# dash-hat.net
KiCad netlist of a schematic drawn in EAGLE
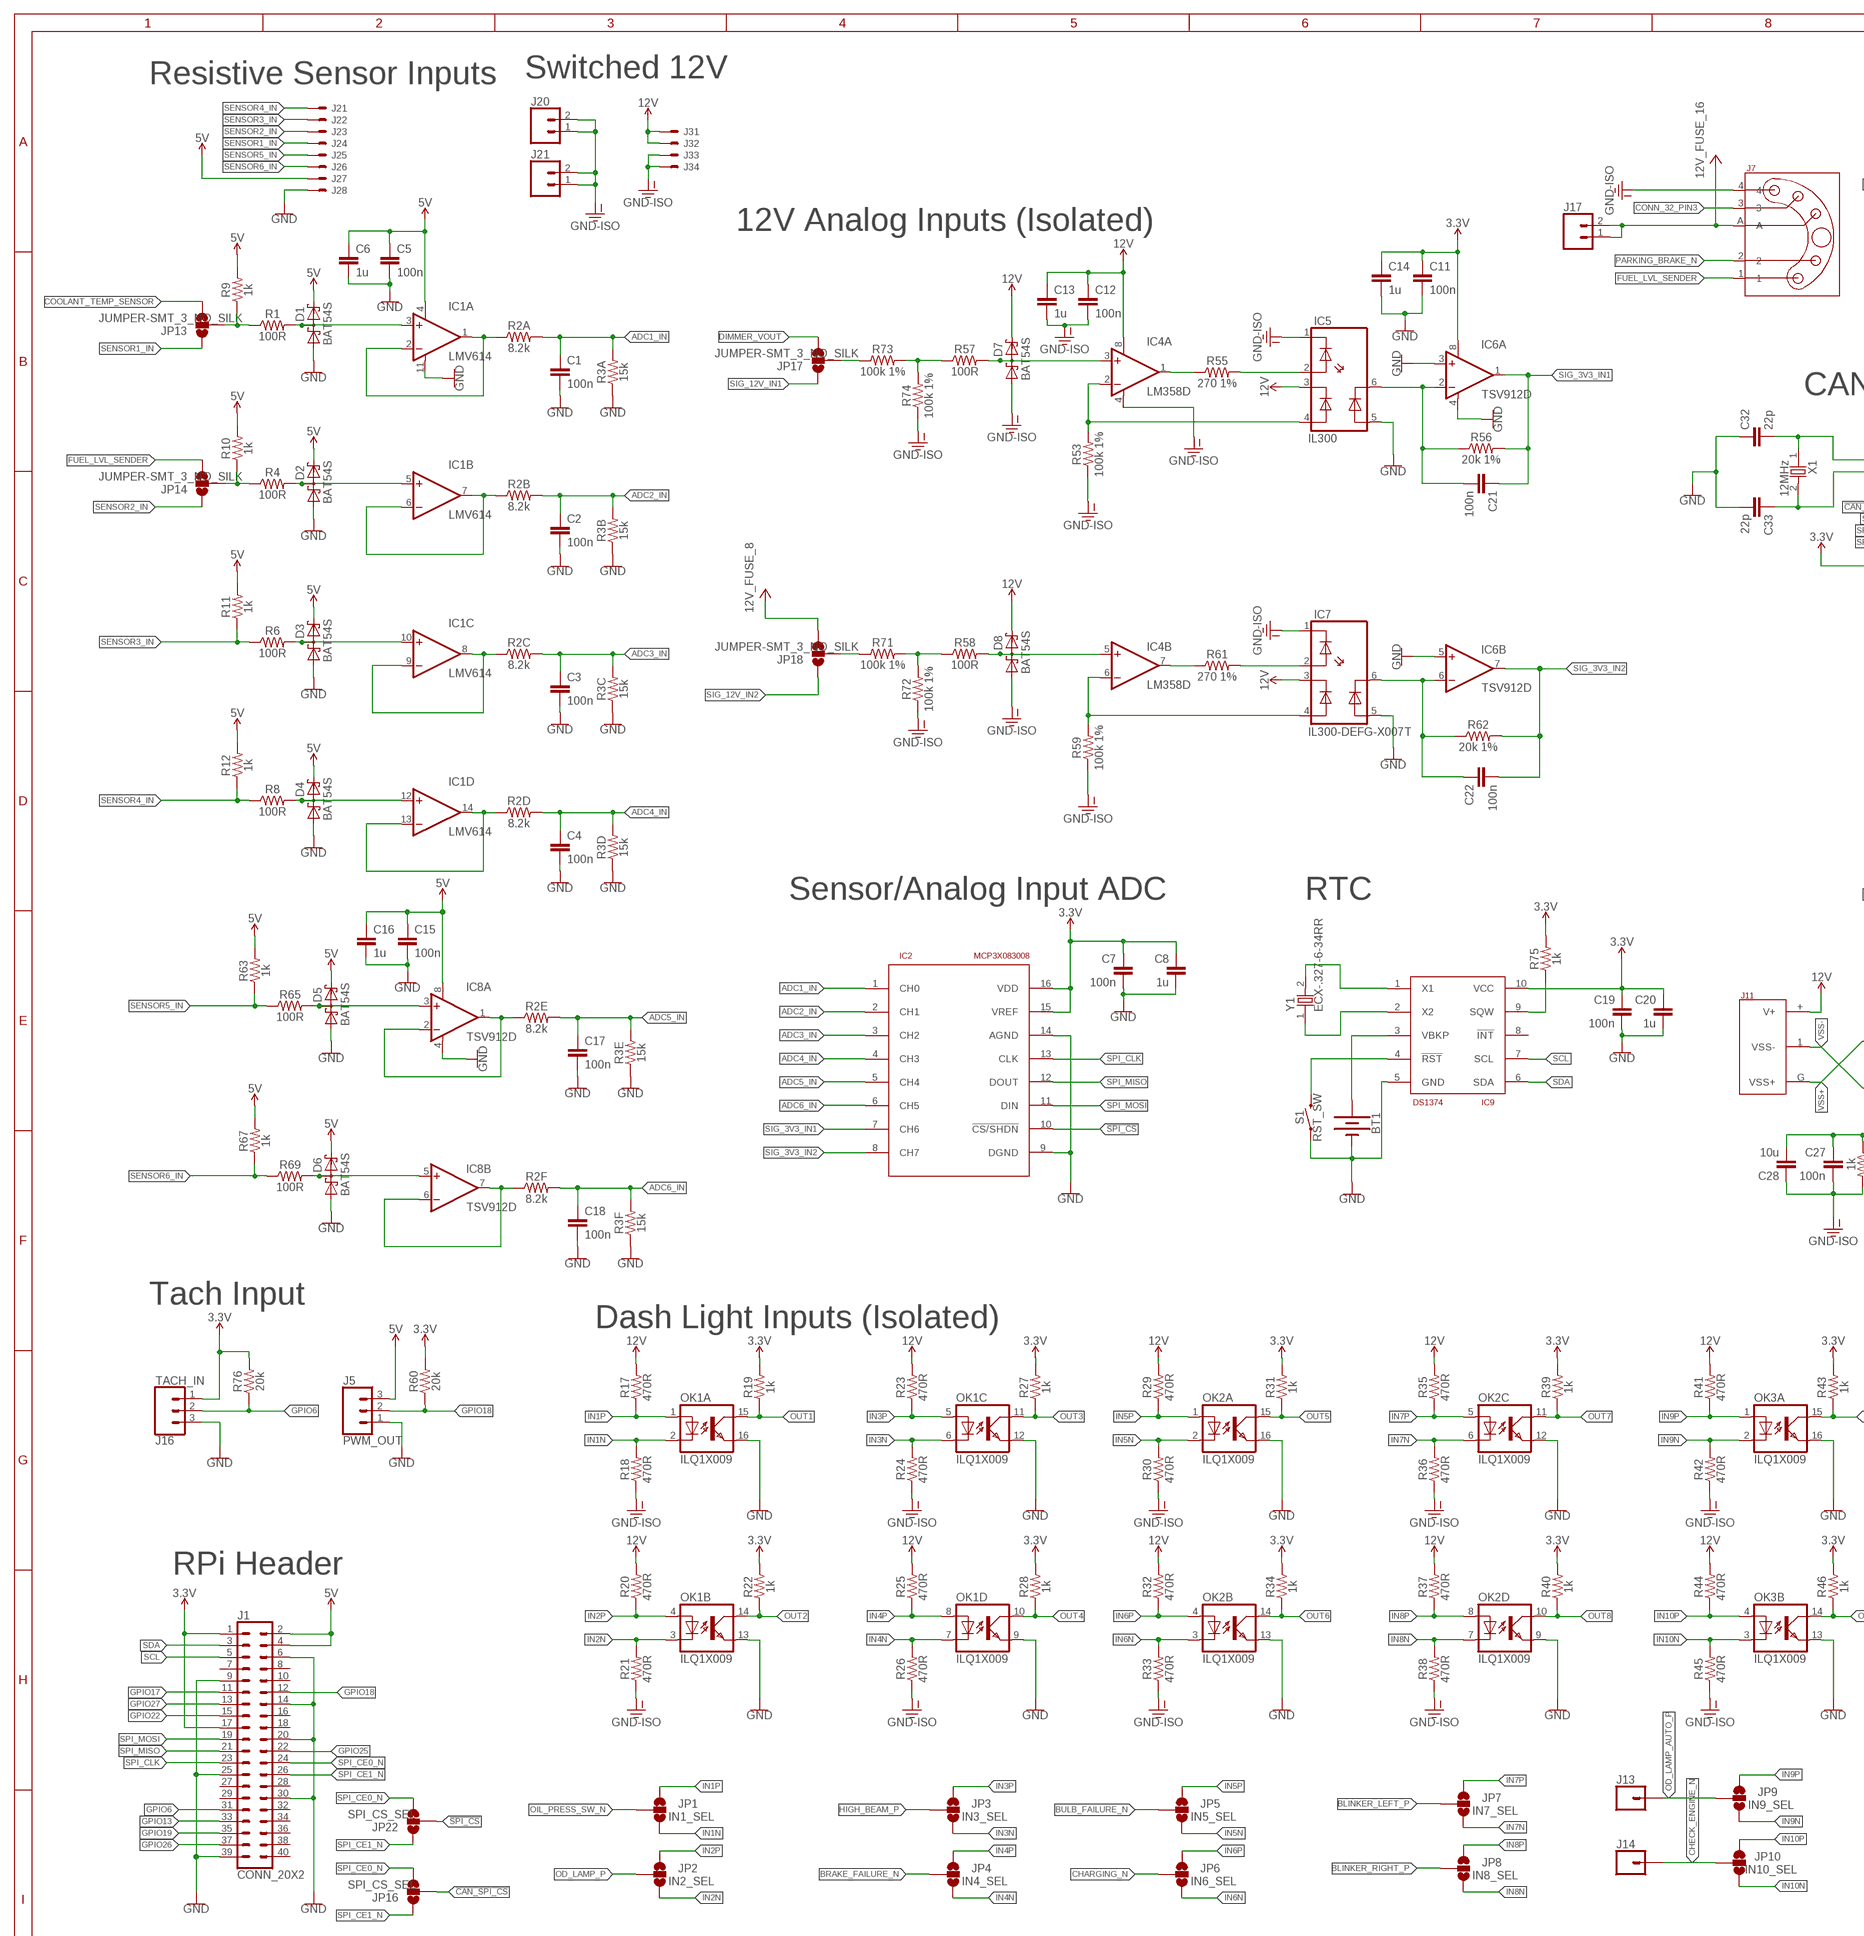
[diagram p0: schematic, sheet 1, part 1 of 2]
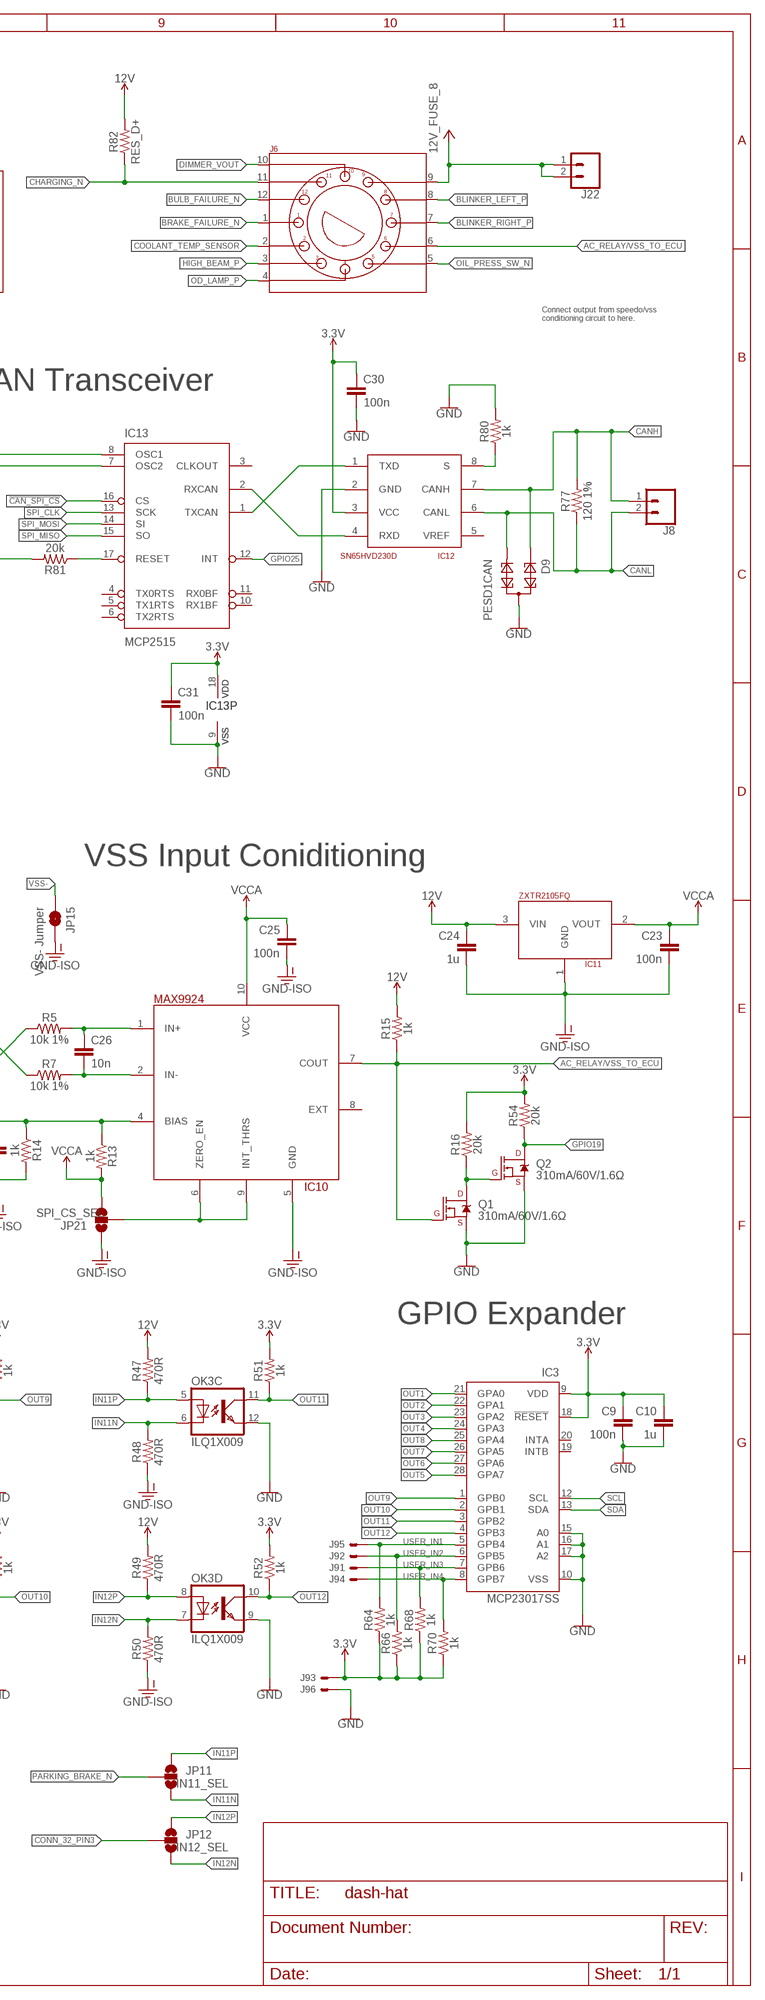
[diagram p1: schematic, sheet 1, part 2 of 2]

(export (version "E")
  (design (tool "Eeschema 10.0.6"))
  (components
    (comp (ref "BT1")
      (value "BATTERY-12MM_SMD")
      (footprint "eagle-import:BATTCON_12MM")
      (libsource (lib "eagle-import") (part "BATTERY-12MM_SMD"))
    )
    (comp (ref "C1")
      (value "100n")
      (footprint "eagle-import:0603")
      (fields (field (name "VOLTAGE") "50V"))
      (libsource (lib "eagle-import") (part "CL10B104MB8NNNC"))
    )
    (comp (ref "C2")
      (value "100n")
      (footprint "eagle-import:0603")
      (fields (field (name "VOLTAGE") "50V"))
      (libsource (lib "eagle-import") (part "CL10B104MB8NNNC"))
    )
    (comp (ref "C3")
      (value "100n")
      (footprint "eagle-import:0603")
      (fields (field (name "VOLTAGE") "50V"))
      (libsource (lib "eagle-import") (part "CL10B104MB8NNNC"))
    )
    (comp (ref "C4")
      (value "100n")
      (footprint "eagle-import:0603")
      (fields (field (name "VOLTAGE") "50V"))
      (libsource (lib "eagle-import") (part "CL10B104MB8NNNC"))
    )
    (comp (ref "C5")
      (value "100n")
      (footprint "eagle-import:0603")
      (fields (field (name "VOLTAGE") "50V"))
      (libsource (lib "eagle-import") (part "CL10B104MB8NNNC"))
    )
    (comp (ref "C6")
      (value "1u")
      (footprint "eagle-import:0603")
      (fields (field (name "VOLTAGE") "25V"))
      (libsource (lib "eagle-import") (part "CL10A105KA8NNNC"))
    )
    (comp (ref "C7")
      (value "100n")
      (footprint "eagle-import:0603")
      (fields (field (name "VOLTAGE") "50V"))
      (libsource (lib "eagle-import") (part "CL10B104MB8NNNC"))
    )
    (comp (ref "C8")
      (value "1u")
      (footprint "eagle-import:0603")
      (fields (field (name "VOLTAGE") "25V"))
      (libsource (lib "eagle-import") (part "CL10A105KA8NNNC"))
    )
    (comp (ref "C9")
      (value "100n")
      (footprint "eagle-import:0603")
      (fields (field (name "VOLTAGE") "50V"))
      (libsource (lib "eagle-import") (part "CL10B104MB8NNNC"))
    )
    (comp (ref "C10")
      (value "1u")
      (footprint "eagle-import:0603")
      (fields (field (name "VOLTAGE") "25V"))
      (libsource (lib "eagle-import") (part "CL10A105KA8NNNC"))
    )
    (comp (ref "C11")
      (value "100n")
      (footprint "eagle-import:0603")
      (fields (field (name "VOLTAGE") "50V"))
      (libsource (lib "eagle-import") (part "CL10B104MB8NNNC"))
    )
    (comp (ref "C12")
      (value "100n")
      (footprint "eagle-import:0603")
      (fields (field (name "VOLTAGE") "50V"))
      (libsource (lib "eagle-import") (part "CL10B104MB8NNNC"))
    )
    (comp (ref "C13")
      (value "1u")
      (footprint "eagle-import:0603")
      (fields (field (name "VOLTAGE") "25V"))
      (libsource (lib "eagle-import") (part "CL10A105KA8NNNC"))
    )
    (comp (ref "C14")
      (value "1u")
      (footprint "eagle-import:0603")
      (fields (field (name "VOLTAGE") "25V"))
      (libsource (lib "eagle-import") (part "CL10A105KA8NNNC"))
    )
    (comp (ref "C15")
      (value "100n")
      (footprint "eagle-import:0603")
      (fields (field (name "VOLTAGE") "50V"))
      (libsource (lib "eagle-import") (part "CL10B104MB8NNNC"))
    )
    (comp (ref "C16")
      (value "1u")
      (footprint "eagle-import:0603")
      (fields (field (name "VOLTAGE") "25V"))
      (libsource (lib "eagle-import") (part "CL10A105KA8NNNC"))
    )
    (comp (ref "C17")
      (value "100n")
      (footprint "eagle-import:0603")
      (fields (field (name "VOLTAGE") "50V"))
      (libsource (lib "eagle-import") (part "CL10B104MB8NNNC"))
    )
    (comp (ref "C18")
      (value "100n")
      (footprint "eagle-import:0603")
      (fields (field (name "VOLTAGE") "50V"))
      (libsource (lib "eagle-import") (part "CL10B104MB8NNNC"))
    )
    (comp (ref "C19")
      (value "100n")
      (footprint "eagle-import:0603")
      (fields (field (name "VOLTAGE") "50V"))
      (libsource (lib "eagle-import") (part "CL10B104MB8NNNC"))
    )
    (comp (ref "C20")
      (value "1u")
      (footprint "eagle-import:0603")
      (fields (field (name "VOLTAGE") "25V"))
      (libsource (lib "eagle-import") (part "CL10A105KA8NNNC"))
    )
    (comp (ref "C21")
      (value "100n")
      (footprint "eagle-import:0603")
      (fields (field (name "VOLTAGE") "50V"))
      (libsource (lib "eagle-import") (part "CL10B104MB8NNNC"))
    )
    (comp (ref "C22")
      (value "100n")
      (footprint "eagle-import:0603")
      (fields (field (name "VOLTAGE") "50V"))
      (libsource (lib "eagle-import") (part "CL10B104MB8NNNC"))
    )
    (comp (ref "C23")
      (value "100n")
      (footprint "eagle-import:0603")
      (fields (field (name "VOLTAGE") "50V"))
      (libsource (lib "eagle-import") (part "CL10B104MB8NNNC"))
    )
    (comp (ref "C24")
      (value "1u")
      (footprint "eagle-import:0603")
      (fields (field (name "VOLTAGE") "25V"))
      (libsource (lib "eagle-import") (part "CL10A105KA8NNNC"))
    )
    (comp (ref "C25")
      (value "100n")
      (footprint "eagle-import:0603")
      (fields (field (name "VOLTAGE") "50V"))
      (libsource (lib "eagle-import") (part "CL10B104MB8NNNC"))
    )
    (comp (ref "C26")
      (value "10n")
      (footprint "eagle-import:0603")
      (fields (field (name "VOLTAGE") "50V"))
      (libsource (lib "eagle-import") (part "CL10B103KB8NNNC"))
    )
    (comp (ref "C27")
      (value "100n")
      (footprint "eagle-import:0603")
      (fields (field (name "VOLTAGE") "50V"))
      (libsource (lib "eagle-import") (part "CL10B104MB8NNNC"))
    )
    (comp (ref "C28")
      (value "10u")
      (footprint "eagle-import:0603")
      (fields (field (name "VOLTAGE") "6.3V"))
      (libsource (lib "eagle-import") (part "CL10B106MQ8NRNC"))
    )
    (comp (ref "C30")
      (value "100n")
      (footprint "eagle-import:0603")
      (fields (field (name "VOLTAGE") "50V"))
      (libsource (lib "eagle-import") (part "CL10B104MB8NNNC"))
    )
    (comp (ref "C31")
      (value "100n")
      (footprint "eagle-import:0603")
      (fields (field (name "VOLTAGE") "50V"))
      (libsource (lib "eagle-import") (part "CL10B104MB8NNNC"))
    )
    (comp (ref "C32")
      (value "22p")
      (footprint "eagle-import:0603")
      (fields (field (name "VOLTAGE") "50V"))
      (libsource (lib "eagle-import") (part "CL10C220JB81PNC"))
    )
    (comp (ref "C33")
      (value "22p")
      (footprint "eagle-import:0603")
      (fields (field (name "VOLTAGE") "50V"))
      (libsource (lib "eagle-import") (part "CL10C220JB81PNC"))
    )
    (comp (ref "D1")
      (value "BAT54S")
      (footprint "eagle-import:SOT23")
      (libsource (lib "eagle-import") (part "BAT54S"))
    )
    (comp (ref "D2")
      (value "BAT54S")
      (footprint "eagle-import:SOT23")
      (libsource (lib "eagle-import") (part "BAT54S"))
    )
    (comp (ref "D3")
      (value "BAT54S")
      (footprint "eagle-import:SOT23")
      (libsource (lib "eagle-import") (part "BAT54S"))
    )
    (comp (ref "D4")
      (value "BAT54S")
      (footprint "eagle-import:SOT23")
      (libsource (lib "eagle-import") (part "BAT54S"))
    )
    (comp (ref "D5")
      (value "BAT54S")
      (footprint "eagle-import:SOT23")
      (libsource (lib "eagle-import") (part "BAT54S"))
    )
    (comp (ref "D6")
      (value "BAT54S")
      (footprint "eagle-import:SOT23")
      (libsource (lib "eagle-import") (part "BAT54S"))
    )
    (comp (ref "D7")
      (value "BAT54S")
      (footprint "eagle-import:SOT23")
      (libsource (lib "eagle-import") (part "BAT54S"))
    )
    (comp (ref "D8")
      (value "BAT54S")
      (footprint "eagle-import:SOT23")
      (libsource (lib "eagle-import") (part "BAT54S"))
    )
    (comp (ref "D9")
      (value "PESD1CAN")
      (footprint "eagle-import:SOT23")
      (libsource (lib "eagle-import") (part "PESD1CAN"))
    )
    (comp (ref "IC1")
      (value "LMV614")
      (footprint "eagle-import:TSSOP14")
      (libsource (lib "eagle-import") (part "LMV614"))
    )
    (comp (ref "IC2")
      (value "MCP3X083008")
      (footprint "eagle-import:SO16")
      (libsource (lib "eagle-import") (part "MCP3X083008"))
    )
    (comp (ref "IC3")
      (value "MCP23017SS")
      (footprint "eagle-import:SSOP28")
      (fields (field (name "MF") "MICROCHIP") (field (name "MPN") "MCP23017-E/SS"))
      (libsource (lib "eagle-import") (part "MCP23017SS"))
    )
    (comp (ref "IC4")
      (value "LM358D")
      (footprint "eagle-import:SO08")
      (libsource (lib "eagle-import") (part "LM358D"))
    )
    (comp (ref "IC5")
      (value "IL300")
      (footprint "eagle-import:DIL8-SMD")
      (libsource (lib "eagle-import") (part "IL300"))
    )
    (comp (ref "IC6")
      (value "TSV912D")
      (footprint "eagle-import:SO08")
      (libsource (lib "eagle-import") (part "TSV912D"))
    )
    (comp (ref "IC7")
      (value "IL300-DEFG-X007T")
      (footprint "eagle-import:DIL8-SMD")
      (libsource (lib "eagle-import") (part "IL300-DEFG-X007T"))
    )
    (comp (ref "IC8")
      (value "TSV912D")
      (footprint "eagle-import:SO08")
      (libsource (lib "eagle-import") (part "TSV912D"))
    )
    (comp (ref "IC9")
      (value "DS1374")
      (footprint "eagle-import:UMAX10")
      (libsource (lib "eagle-import") (part "DS1374"))
    )
    (comp (ref "IC10")
      (value "MAX9924")
      (footprint "eagle-import:UMAX10")
      (libsource (lib "eagle-import") (part "MAX9924"))
    )
    (comp (ref "IC11")
      (value "ZXTR2105FQ")
      (footprint "eagle-import:SOT23")
      (libsource (lib "eagle-import") (part "ZXTR2105FQ"))
    )
    (comp (ref "IC12")
      (value "SN65HVD230D")
      (footprint "eagle-import:SO08")
      (libsource (lib "eagle-import") (part "SN65HVD230D"))
    )
    (comp (ref "IC13")
      (value "MCP2515")
      (footprint "eagle-import:SO18W")
      (libsource (lib "eagle-import") (part "MCP2515(MCP2510)SO"))
    )
    (comp (ref "J1")
      (value "CONN_20X2")
      (footprint "eagle-import:2X20")
      (libsource (lib "eagle-import") (part "CONN_20X2"))
    )
    (comp (ref "J2")
      (value "CONN_04X2")
      (footprint "eagle-import:MOLEX-1053102108")
      (libsource (lib "eagle-import") (part "CONN_04X2"))
    )
    (comp (ref "J3")
      (value "CONN_04RIGHT-ANGLE")
      (footprint "eagle-import:MOLEX-1053141204")
      (libsource (lib "eagle-import") (part "CONN_04RIGHT-ANGLE"))
    )
    (comp (ref "J5")
      (value "PWM_OUT")
      (footprint "eagle-import:1X03_JST-XHP")
      (libsource (lib "eagle-import") (part "CONN_03JST-XHP"))
    )
    (comp (ref "J6")
      (value "VOLVO_CONN_31")
      (footprint "eagle-import:VOLVO_CON_31")
      (libsource (lib "eagle-import") (part "VOLVO_CONN_31"))
    )
    (comp (ref "J7")
      (value "VOLVO_CONN_32")
      (footprint "eagle-import:VOLVO_CON_32")
      (libsource (lib "eagle-import") (part "VOLVO_CONN_32"))
    )
    (comp (ref "J8")
      (value "CONN_02JST-XHP")
      (footprint "eagle-import:1X02_JST-XHP")
      (libsource (lib "eagle-import") (part "CONN_02JST-XHP"))
    )
    (comp (ref "J9")
      (value "CONN_03X2")
      (footprint "eagle-import:MOLEX-1053101106")
      (libsource (lib "eagle-import") (part "CONN_03X2"))
    )
    (comp (ref "J11")
      (value "VOLVO_CONN_VSS")
      (footprint "eagle-import:VOLVO_CONN_VSS")
      (libsource (lib "eagle-import") (part "VOLVO_CONN_VSS"))
    )
    (comp (ref "J13")
      (value "CONN_01PTH_2MM")
      (footprint "eagle-import:1X01_2MM")
      (libsource (lib "eagle-import") (part "CONN_01PTH_2MM"))
    )
    (comp (ref "J14")
      (value "CONN_01PTH_2MM")
      (footprint "eagle-import:1X01_2MM")
      (libsource (lib "eagle-import") (part "CONN_01PTH_2MM"))
    )
    (comp (ref "J16")
      (value "TACH_IN")
      (footprint "eagle-import:1X03_JST-XHP")
      (libsource (lib "eagle-import") (part "CONN_03JST-XHP"))
    )
    (comp (ref "J17")
      (value "CONN_02PTH4")
      (footprint "eagle-import:1X02_XTRA_BIG")
      (libsource (lib "eagle-import") (part "CONN_02PTH4"))
    )
    (comp (ref "J20")
      (value "CONN_02PTH4")
      (footprint "eagle-import:1X02_XTRA_BIG")
      (libsource (lib "eagle-import") (part "CONN_02PTH4"))
    )
    (comp (ref "J21")
      (value "CONN_02PTH4")
      (footprint "eagle-import:1X02_XTRA_BIG")
      (libsource (lib "eagle-import") (part "CONN_02PTH4"))
    )
    (comp (ref "J22")
      (value "CONN_02PTH4")
      (footprint "eagle-import:1X02_XTRA_BIG")
      (libsource (lib "eagle-import") (part "CONN_02PTH4"))
    )
    (comp (ref "JP1")
      (value "IN1_SEL")
      (footprint "eagle-import:SMT-JUMPER_3_NO_SILK")
      (libsource (lib "eagle-import") (part "JUMPER-SMT_3_NO_SILK"))
    )
    (comp (ref "JP2")
      (value "IN2_SEL")
      (footprint "eagle-import:SMT-JUMPER_3_NO_SILK")
      (libsource (lib "eagle-import") (part "JUMPER-SMT_3_NO_SILK"))
    )
    (comp (ref "JP3")
      (value "IN3_SEL")
      (footprint "eagle-import:SMT-JUMPER_3_NO_SILK")
      (libsource (lib "eagle-import") (part "JUMPER-SMT_3_NO_SILK"))
    )
    (comp (ref "JP4")
      (value "IN4_SEL")
      (footprint "eagle-import:SMT-JUMPER_3_NO_SILK")
      (libsource (lib "eagle-import") (part "JUMPER-SMT_3_NO_SILK"))
    )
    (comp (ref "JP5")
      (value "IN5_SEL")
      (footprint "eagle-import:SMT-JUMPER_3_NO_SILK")
      (libsource (lib "eagle-import") (part "JUMPER-SMT_3_NO_SILK"))
    )
    (comp (ref "JP6")
      (value "IN6_SEL")
      (footprint "eagle-import:SMT-JUMPER_3_NO_SILK")
      (libsource (lib "eagle-import") (part "JUMPER-SMT_3_NO_SILK"))
    )
    (comp (ref "JP7")
      (value "IN7_SEL")
      (footprint "eagle-import:SMT-JUMPER_3_NO_SILK")
      (libsource (lib "eagle-import") (part "JUMPER-SMT_3_NO_SILK"))
    )
    (comp (ref "JP8")
      (value "IN8_SEL")
      (footprint "eagle-import:SMT-JUMPER_3_NO_SILK")
      (libsource (lib "eagle-import") (part "JUMPER-SMT_3_NO_SILK"))
    )
    (comp (ref "JP9")
      (value "IN9_SEL")
      (footprint "eagle-import:SMT-JUMPER_3_NO_SILK")
      (libsource (lib "eagle-import") (part "JUMPER-SMT_3_NO_SILK"))
    )
    (comp (ref "JP10")
      (value "IN10_SEL")
      (footprint "eagle-import:SMT-JUMPER_3_NO_SILK")
      (libsource (lib "eagle-import") (part "JUMPER-SMT_3_NO_SILK"))
    )
    (comp (ref "JP11")
      (value "IN11_SEL")
      (footprint "eagle-import:SMT-JUMPER_3_NO_SILK")
      (libsource (lib "eagle-import") (part "JUMPER-SMT_3_NO_SILK"))
    )
    (comp (ref "JP12")
      (value "IN12_SEL")
      (footprint "eagle-import:SMT-JUMPER_3_NO_SILK")
      (libsource (lib "eagle-import") (part "JUMPER-SMT_3_NO_SILK"))
    )
    (comp (ref "JP13")
      (value "JUMPER-SMT_3_NO_SILK")
      (footprint "eagle-import:SMT-JUMPER_3_NO_SILK")
      (libsource (lib "eagle-import") (part "JUMPER-SMT_3_NO_SILK"))
    )
    (comp (ref "JP14")
      (value "JUMPER-SMT_3_NO_SILK")
      (footprint "eagle-import:SMT-JUMPER_3_NO_SILK")
      (libsource (lib "eagle-import") (part "JUMPER-SMT_3_NO_SILK"))
    )
    (comp (ref "JP15")
      (value "VSS- Jumper")
      (footprint "eagle-import:SMT-JUMPER_2_NO_SILK")
      (libsource (lib "eagle-import") (part "JUMPER-SMT_2_NO_SILK"))
    )
    (comp (ref "JP16")
      (value "SPI_CS_SEL")
      (footprint "eagle-import:SMT-JUMPER_3_NO_SILK")
      (libsource (lib "eagle-import") (part "JUMPER-SMT_3_NO_SILK"))
    )
    (comp (ref "JP17")
      (value "JUMPER-SMT_3_NO_SILK")
      (footprint "eagle-import:SMT-JUMPER_3_NO_SILK")
      (libsource (lib "eagle-import") (part "JUMPER-SMT_3_NO_SILK"))
    )
    (comp (ref "JP18")
      (value "JUMPER-SMT_3_NO_SILK")
      (footprint "eagle-import:SMT-JUMPER_3_NO_SILK")
      (libsource (lib "eagle-import") (part "JUMPER-SMT_3_NO_SILK"))
    )
    (comp (ref "JP21")
      (value "SPI_CS_SEL")
      (footprint "eagle-import:SMT-JUMPER_3_NO_SILK")
      (libsource (lib "eagle-import") (part "JUMPER-SMT_3_NO_SILK"))
    )
    (comp (ref "JP22")
      (value "SPI_CS_SEL")
      (footprint "eagle-import:SMT-JUMPER_3_NO_SILK")
      (libsource (lib "eagle-import") (part "JUMPER-SMT_3_NO_SILK"))
    )
    (comp (ref "OK1")
      (value "ILQ1X009")
      (footprint "eagle-import:SMD16")
      (libsource (lib "eagle-import") (part "ILQ1X009"))
    )
    (comp (ref "OK2")
      (value "ILQ1X009")
      (footprint "eagle-import:SMD16")
      (libsource (lib "eagle-import") (part "ILQ1X009"))
    )
    (comp (ref "OK3")
      (value "ILQ1X009")
      (footprint "eagle-import:SMD16")
      (libsource (lib "eagle-import") (part "ILQ1X009"))
    )
    (comp (ref "Q1")
      (value "310mA/60V/1.6Ω")
      (footprint "eagle-import:SOT323")
      (libsource (lib "eagle-import") (part "MOSFET-NCH-2N7002PW"))
    )
    (comp (ref "Q2")
      (value "310mA/60V/1.6Ω")
      (footprint "eagle-import:SOT323")
      (libsource (lib "eagle-import") (part "MOSFET-NCH-2N7002PW"))
    )
    (comp (ref "R1")
      (value "100R")
      (footprint "eagle-import:0603")
      (libsource (lib "eagle-import") (part "RC0603JR-07100RL"))
    )
    (comp (ref "R2")
      (value "8.2k")
      (footprint "eagle-import:YC248")
      (fields (field (name "TOLERANCE") "5%"))
      (libsource (lib "eagle-import") (part "YC248-JR-078K2L"))
    )
    (comp (ref "R3")
      (value "15k")
      (footprint "eagle-import:YC248")
      (fields (field (name "TOLERANCE") "5%"))
      (libsource (lib "eagle-import") (part "YC248-JR-0715KL"))
    )
    (comp (ref "R4")
      (value "100R")
      (footprint "eagle-import:0603")
      (libsource (lib "eagle-import") (part "RC0603JR-07100RL"))
    )
    (comp (ref "R5")
      (value "10k 1%")
      (footprint "eagle-import:0603")
      (libsource (lib "eagle-import") (part "RC0603FR-1010KL"))
    )
    (comp (ref "R6")
      (value "100R")
      (footprint "eagle-import:0603")
      (libsource (lib "eagle-import") (part "RC0603JR-07100RL"))
    )
    (comp (ref "R7")
      (value "10k 1%")
      (footprint "eagle-import:0603")
      (libsource (lib "eagle-import") (part "RC0603FR-1010KL"))
    )
    (comp (ref "R8")
      (value "100R")
      (footprint "eagle-import:0603")
      (libsource (lib "eagle-import") (part "RC0603JR-07100RL"))
    )
    (comp (ref "R9")
      (value "1k")
      (footprint "eagle-import:0603")
      (libsource (lib "eagle-import") (part "RC0603JR-071KL"))
    )
    (comp (ref "R10")
      (value "1k")
      (footprint "eagle-import:0603")
      (libsource (lib "eagle-import") (part "RC0603JR-071KL"))
    )
    (comp (ref "R11")
      (value "1k")
      (footprint "eagle-import:0603")
      (libsource (lib "eagle-import") (part "RC0603JR-071KL"))
    )
    (comp (ref "R12")
      (value "1k")
      (footprint "eagle-import:0603")
      (libsource (lib "eagle-import") (part "RC0603JR-071KL"))
    )
    (comp (ref "R13")
      (value "1k")
      (footprint "eagle-import:0603")
      (libsource (lib "eagle-import") (part "RC0603JR-071KL"))
    )
    (comp (ref "R14")
      (value "1k")
      (footprint "eagle-import:0603")
      (libsource (lib "eagle-import") (part "RC0603JR-071KL"))
    )
    (comp (ref "R15")
      (value "1k")
      (footprint "eagle-import:0603")
      (libsource (lib "eagle-import") (part "RC0603JR-071KL"))
    )
    (comp (ref "R16")
      (value "20k")
      (footprint "eagle-import:0603")
      (libsource (lib "eagle-import") (part "RC0603JR-0720KL"))
    )
    (comp (ref "R17")
      (value "470R")
      (footprint "eagle-import:0603")
      (libsource (lib "eagle-import") (part "RC0603JR-07470RL"))
    )
    (comp (ref "R18")
      (value "470R")
      (footprint "eagle-import:0603")
      (libsource (lib "eagle-import") (part "RC0603JR-07470RL"))
    )
    (comp (ref "R19")
      (value "1k")
      (footprint "eagle-import:0603")
      (libsource (lib "eagle-import") (part "RC0603JR-071KL"))
    )
    (comp (ref "R20")
      (value "470R")
      (footprint "eagle-import:0603")
      (libsource (lib "eagle-import") (part "RC0603JR-07470RL"))
    )
    (comp (ref "R21")
      (value "470R")
      (footprint "eagle-import:0603")
      (libsource (lib "eagle-import") (part "RC0603JR-07470RL"))
    )
    (comp (ref "R22")
      (value "1k")
      (footprint "eagle-import:0603")
      (libsource (lib "eagle-import") (part "RC0603JR-071KL"))
    )
    (comp (ref "R23")
      (value "470R")
      (footprint "eagle-import:0603")
      (libsource (lib "eagle-import") (part "RC0603JR-07470RL"))
    )
    (comp (ref "R24")
      (value "470R")
      (footprint "eagle-import:0603")
      (libsource (lib "eagle-import") (part "RC0603JR-07470RL"))
    )
    (comp (ref "R25")
      (value "470R")
      (footprint "eagle-import:0603")
      (libsource (lib "eagle-import") (part "RC0603JR-07470RL"))
    )
    (comp (ref "R26")
      (value "470R")
      (footprint "eagle-import:0603")
      (libsource (lib "eagle-import") (part "RC0603JR-07470RL"))
    )
    (comp (ref "R27")
      (value "1k")
      (footprint "eagle-import:0603")
      (libsource (lib "eagle-import") (part "RC0603JR-071KL"))
    )
    (comp (ref "R28")
      (value "1k")
      (footprint "eagle-import:0603")
      (libsource (lib "eagle-import") (part "RC0603JR-071KL"))
    )
    (comp (ref "R29")
      (value "470R")
      (footprint "eagle-import:0603")
      (libsource (lib "eagle-import") (part "RC0603JR-07470RL"))
    )
    (comp (ref "R30")
      (value "470R")
      (footprint "eagle-import:0603")
      (libsource (lib "eagle-import") (part "RC0603JR-07470RL"))
    )
    (comp (ref "R31")
      (value "1k")
      (footprint "eagle-import:0603")
      (libsource (lib "eagle-import") (part "RC0603JR-071KL"))
    )
    (comp (ref "R32")
      (value "470R")
      (footprint "eagle-import:0603")
      (libsource (lib "eagle-import") (part "RC0603JR-07470RL"))
    )
    (comp (ref "R33")
      (value "470R")
      (footprint "eagle-import:0603")
      (libsource (lib "eagle-import") (part "RC0603JR-07470RL"))
    )
    (comp (ref "R34")
      (value "1k")
      (footprint "eagle-import:0603")
      (libsource (lib "eagle-import") (part "RC0603JR-071KL"))
    )
    (comp (ref "R35")
      (value "470R")
      (footprint "eagle-import:0603")
      (libsource (lib "eagle-import") (part "RC0603JR-07470RL"))
    )
    (comp (ref "R36")
      (value "470R")
      (footprint "eagle-import:0603")
      (libsource (lib "eagle-import") (part "RC0603JR-07470RL"))
    )
    (comp (ref "R37")
      (value "470R")
      (footprint "eagle-import:0603")
      (libsource (lib "eagle-import") (part "RC0603JR-07470RL"))
    )
    (comp (ref "R38")
      (value "470R")
      (footprint "eagle-import:0603")
      (libsource (lib "eagle-import") (part "RC0603JR-07470RL"))
    )
    (comp (ref "R39")
      (value "1k")
      (footprint "eagle-import:0603")
      (libsource (lib "eagle-import") (part "RC0603JR-071KL"))
    )
    (comp (ref "R40")
      (value "1k")
      (footprint "eagle-import:0603")
      (libsource (lib "eagle-import") (part "RC0603JR-071KL"))
    )
    (comp (ref "R41")
      (value "470R")
      (footprint "eagle-import:0603")
      (libsource (lib "eagle-import") (part "RC0603JR-07470RL"))
    )
    (comp (ref "R42")
      (value "470R")
      (footprint "eagle-import:0603")
      (libsource (lib "eagle-import") (part "RC0603JR-07470RL"))
    )
    (comp (ref "R43")
      (value "1k")
      (footprint "eagle-import:0603")
      (libsource (lib "eagle-import") (part "RC0603JR-071KL"))
    )
    (comp (ref "R44")
      (value "470R")
      (footprint "eagle-import:0603")
      (libsource (lib "eagle-import") (part "RC0603JR-07470RL"))
    )
    (comp (ref "R45")
      (value "470R")
      (footprint "eagle-import:0603")
      (libsource (lib "eagle-import") (part "RC0603JR-07470RL"))
    )
    (comp (ref "R46")
      (value "1k")
      (footprint "eagle-import:0603")
      (libsource (lib "eagle-import") (part "RC0603JR-071KL"))
    )
    (comp (ref "R47")
      (value "470R")
      (footprint "eagle-import:0603")
      (libsource (lib "eagle-import") (part "RC0603JR-07470RL"))
    )
    (comp (ref "R48")
      (value "470R")
      (footprint "eagle-import:0603")
      (libsource (lib "eagle-import") (part "RC0603JR-07470RL"))
    )
    (comp (ref "R49")
      (value "470R")
      (footprint "eagle-import:0603")
      (libsource (lib "eagle-import") (part "RC0603JR-07470RL"))
    )
    (comp (ref "R50")
      (value "470R")
      (footprint "eagle-import:0603")
      (libsource (lib "eagle-import") (part "RC0603JR-07470RL"))
    )
    (comp (ref "R51")
      (value "1k")
      (footprint "eagle-import:0603")
      (libsource (lib "eagle-import") (part "RC0603JR-071KL"))
    )
    (comp (ref "R52")
      (value "1k")
      (footprint "eagle-import:0603")
      (libsource (lib "eagle-import") (part "RC0603JR-071KL"))
    )
    (comp (ref "R53")
      (value "100k 1%")
      (footprint "eagle-import:0603")
      (libsource (lib "eagle-import") (part "RC0603FR-10100KL"))
    )
    (comp (ref "R54")
      (value "20k")
      (footprint "eagle-import:0603")
      (libsource (lib "eagle-import") (part "RC0603JR-0720KL"))
    )
    (comp (ref "R55")
      (value "270 1%")
      (footprint "eagle-import:0603")
      (libsource (lib "eagle-import") (part "RC0603FR-07270RL"))
    )
    (comp (ref "R56")
      (value "20k 1%")
      (footprint "eagle-import:0603")
      (libsource (lib "eagle-import") (part "RC0603FR-0720KL"))
    )
    (comp (ref "R57")
      (value "100R")
      (footprint "eagle-import:0603")
      (libsource (lib "eagle-import") (part "RC0603JR-07100RL"))
    )
    (comp (ref "R58")
      (value "100R")
      (footprint "eagle-import:0603")
      (libsource (lib "eagle-import") (part "RC0603JR-07100RL"))
    )
    (comp (ref "R59")
      (value "100k 1%")
      (footprint "eagle-import:0603")
      (libsource (lib "eagle-import") (part "RC0603FR-10100KL"))
    )
    (comp (ref "R60")
      (value "20k")
      (footprint "eagle-import:0603")
      (libsource (lib "eagle-import") (part "RC0603JR-0720KL"))
    )
    (comp (ref "R61")
      (value "270 1%")
      (footprint "eagle-import:0603")
      (libsource (lib "eagle-import") (part "RC0603FR-07270RL"))
    )
    (comp (ref "R62")
      (value "20k 1%")
      (footprint "eagle-import:0603")
      (libsource (lib "eagle-import") (part "RC0603FR-0720KL"))
    )
    (comp (ref "R63")
      (value "1k")
      (footprint "eagle-import:0603")
      (libsource (lib "eagle-import") (part "RC0603JR-071KL"))
    )
    (comp (ref "R64")
      (value "1k")
      (footprint "eagle-import:0603")
      (libsource (lib "eagle-import") (part "RC0603JR-071KL"))
    )
    (comp (ref "R65")
      (value "100R")
      (footprint "eagle-import:0603")
      (libsource (lib "eagle-import") (part "RC0603JR-07100RL"))
    )
    (comp (ref "R66")
      (value "1k")
      (footprint "eagle-import:0603")
      (libsource (lib "eagle-import") (part "RC0603JR-071KL"))
    )
    (comp (ref "R67")
      (value "1k")
      (footprint "eagle-import:0603")
      (libsource (lib "eagle-import") (part "RC0603JR-071KL"))
    )
    (comp (ref "R68")
      (value "1k")
      (footprint "eagle-import:0603")
      (libsource (lib "eagle-import") (part "RC0603JR-071KL"))
    )
    (comp (ref "R69")
      (value "100R")
      (footprint "eagle-import:0603")
      (libsource (lib "eagle-import") (part "RC0603JR-07100RL"))
    )
    (comp (ref "R70")
      (value "1k")
      (footprint "eagle-import:0603")
      (libsource (lib "eagle-import") (part "RC0603JR-071KL"))
    )
    (comp (ref "R71")
      (value "100k 1%")
      (footprint "eagle-import:0603")
      (libsource (lib "eagle-import") (part "RC0603FR-10100KL"))
    )
    (comp (ref "R72")
      (value "100k 1%")
      (footprint "eagle-import:0603")
      (libsource (lib "eagle-import") (part "RC0603FR-10100KL"))
    )
    (comp (ref "R73")
      (value "100k 1%")
      (footprint "eagle-import:0603")
      (libsource (lib "eagle-import") (part "RC0603FR-10100KL"))
    )
    (comp (ref "R74")
      (value "100k 1%")
      (footprint "eagle-import:0603")
      (libsource (lib "eagle-import") (part "RC0603FR-10100KL"))
    )
    (comp (ref "R75")
      (value "1k")
      (footprint "eagle-import:0603")
      (libsource (lib "eagle-import") (part "RC0603JR-071KL"))
    )
    (comp (ref "R76")
      (value "20k")
      (footprint "eagle-import:0603")
      (libsource (lib "eagle-import") (part "RC0603JR-0720KL"))
    )
    (comp (ref "R77")
      (value "120 1%")
      (footprint "eagle-import:0603")
      (libsource (lib "eagle-import") (part "RC0603FR-07120RL"))
    )
    (comp (ref "R80")
      (value "1k")
      (footprint "eagle-import:0603")
      (libsource (lib "eagle-import") (part "RC0603JR-071KL"))
    )
    (comp (ref "R81")
      (value "20k")
      (footprint "eagle-import:0603")
      (libsource (lib "eagle-import") (part "RC0603JR-0720KL"))
    )
    (comp (ref "R82")
      (value "RES_D+")
      (footprint "eagle-import:0617_17")
      (libsource (lib "eagle-import") (part "RES_D+"))
    )
    (comp (ref "S1")
      (value "RST_SW")
      (footprint "eagle-import:TACTILE_SWITCH_SMD_6.0X3.5MM")
      (libsource (lib "eagle-import") (part "MOMENTARY-SWITCH-SPST-SMD-6.0X3.5MM"))
    )
    (comp (ref "X1")
      (value "12MHz")
      (footprint "eagle-import:ECS")
      (libsource (lib "eagle-import") (part "ECS-120-20-3X-TR"))
    )
    (comp (ref "Y1")
      (value "ECX-.327-6-34RR")
      (footprint "eagle-import:ECX-34RR")
      (libsource (lib "eagle-import") (part "ECX-.327-6-34RR"))
    )
  )
  (nets
    (net (code "1") (name "/USER_IN1") (class "Default")
      (node (ref "IC3") (pin "5") (pinfunction "GPB4_5") (pintype "bidirectional"))
      (node (ref "J9") (pin "5") (pinfunction "S_5") (pintype "passive"))
      (node (ref "R64") (pin "2") (pinfunction "2_2") (pintype "passive"))
    )
    (net (code "2") (name "/USER_IN2") (class "Default")
      (node (ref "IC3") (pin "6") (pinfunction "GPB5_6") (pintype "bidirectional"))
      (node (ref "J9") (pin "2") (pinfunction "S_2") (pintype "passive"))
      (node (ref "R66") (pin "2") (pinfunction "2_2") (pintype "passive"))
    )
    (net (code "3") (name "/USER_IN3") (class "Default")
      (node (ref "IC3") (pin "7") (pinfunction "GPB6_7") (pintype "bidirectional"))
      (node (ref "J9") (pin "1") (pinfunction "S_1") (pintype "passive"))
      (node (ref "R68") (pin "2") (pinfunction "2_2") (pintype "passive"))
    )
    (net (code "4") (name "/USER_IN4") (class "Default")
      (node (ref "IC3") (pin "8") (pinfunction "GPB7_8") (pintype "bidirectional"))
      (node (ref "J9") (pin "4") (pinfunction "S_4") (pintype "passive"))
      (node (ref "R70") (pin "2") (pinfunction "2_2") (pintype "passive"))
    )
    (net (code "5") (name "/~{CAN_SPI_CS}") (class "Default")
      (node (ref "IC13") (pin "16") (pinfunction "CS_16") (pintype "input"))
      (node (ref "JP16") (pin "2") (pinfunction "2_2") (pintype "passive"))
    )
    (net (code "6") (name "/~{SPI_CS}") (class "Default")
      (node (ref "IC2") (pin "10") (pinfunction "~{CS/SHDN}_10") (pintype "bidirectional"))
      (node (ref "JP22") (pin "2") (pinfunction "2_2") (pintype "passive"))
    )
    (net (code "7") (name "3.3V") (class "Default")
      (node (ref "C10") (pin "1") (pinfunction "1_1") (pintype "passive"))
      (node (ref "C11") (pin "1") (pinfunction "1_1") (pintype "passive"))
      (node (ref "C14") (pin "1") (pinfunction "1_1") (pintype "passive"))
      (node (ref "C19") (pin "1") (pinfunction "1_1") (pintype "passive"))
      (node (ref "C20") (pin "1") (pinfunction "1_1") (pintype "passive"))
      (node (ref "C30") (pin "1") (pinfunction "1_1") (pintype "passive"))
      (node (ref "C31") (pin "1") (pinfunction "1_1") (pintype "passive"))
      (node (ref "C7") (pin "1") (pinfunction "1_1") (pintype "passive"))
      (node (ref "C8") (pin "1") (pinfunction "1_1") (pintype "passive"))
      (node (ref "C9") (pin "1") (pinfunction "1_1") (pintype "passive"))
      (node (ref "IC12") (pin "3") (pinfunction "VCC_3") (pintype "bidirectional"))
      (node (ref "IC13") (pin "18") (pinfunction "VDD_18") (pintype "power_in"))
      (node (ref "IC2") (pin "15") (pinfunction "VREF_15") (pintype "bidirectional"))
      (node (ref "IC2") (pin "16") (pinfunction "VDD_16") (pintype "bidirectional"))
      (node (ref "IC3") (pin "18") (pinfunction "~{RESET}_18") (pintype "input"))
      (node (ref "IC3") (pin "9") (pinfunction "VDD_9") (pintype "power_in"))
      (node (ref "IC6") (pin "8") (pinfunction "V+_8") (pintype "power_in"))
      (node (ref "IC9") (pin "10") (pinfunction "VCC_10") (pintype "power_in"))
      (node (ref "J1") (pin "1") (pinfunction "1_1") (pintype "passive"))
      (node (ref "J1") (pin "17") (pinfunction "17_17") (pintype "passive"))
      (node (ref "J16") (pin "1") (pinfunction "1_1") (pintype "passive"))
      (node (ref "J9") (pin "3") (pinfunction "S_3") (pintype "passive"))
      (node (ref "R16") (pin "2") (pinfunction "2_2") (pintype "passive"))
      (node (ref "R19") (pin "2") (pinfunction "2_2") (pintype "passive"))
      (node (ref "R22") (pin "2") (pinfunction "2_2") (pintype "passive"))
      (node (ref "R27") (pin "2") (pinfunction "2_2") (pintype "passive"))
      (node (ref "R28") (pin "2") (pinfunction "2_2") (pintype "passive"))
      (node (ref "R31") (pin "2") (pinfunction "2_2") (pintype "passive"))
      (node (ref "R34") (pin "2") (pinfunction "2_2") (pintype "passive"))
      (node (ref "R39") (pin "2") (pinfunction "2_2") (pintype "passive"))
      (node (ref "R40") (pin "2") (pinfunction "2_2") (pintype "passive"))
      (node (ref "R43") (pin "2") (pinfunction "2_2") (pintype "passive"))
      (node (ref "R46") (pin "2") (pinfunction "2_2") (pintype "passive"))
      (node (ref "R51") (pin "2") (pinfunction "2_2") (pintype "passive"))
      (node (ref "R52") (pin "2") (pinfunction "2_2") (pintype "passive"))
      (node (ref "R54") (pin "2") (pinfunction "2_2") (pintype "passive"))
      (node (ref "R60") (pin "2") (pinfunction "2_2") (pintype "passive"))
      (node (ref "R64") (pin "1") (pinfunction "1_1") (pintype "passive"))
      (node (ref "R66") (pin "1") (pinfunction "1_1") (pintype "passive"))
      (node (ref "R68") (pin "1") (pinfunction "1_1") (pintype "passive"))
      (node (ref "R70") (pin "1") (pinfunction "1_1") (pintype "passive"))
      (node (ref "R75") (pin "2") (pinfunction "2_2") (pintype "passive"))
      (node (ref "R76") (pin "2") (pinfunction "2_2") (pintype "passive"))
      (node (ref "R81") (pin "2") (pinfunction "2_2") (pintype "passive"))
    )
    (net (code "8") (name "5V") (class "Default")
      (node (ref "C15") (pin "1") (pinfunction "1_1") (pintype "passive"))
      (node (ref "C16") (pin "1") (pinfunction "1_1") (pintype "passive"))
      (node (ref "C5") (pin "1") (pinfunction "1_1") (pintype "passive"))
      (node (ref "C6") (pin "1") (pinfunction "1_1") (pintype "passive"))
      (node (ref "D1") (pin "2") (pinfunction "C2_2") (pintype "passive"))
      (node (ref "D2") (pin "2") (pinfunction "C2_2") (pintype "passive"))
      (node (ref "D3") (pin "2") (pinfunction "C2_2") (pintype "passive"))
      (node (ref "D4") (pin "2") (pinfunction "C2_2") (pintype "passive"))
      (node (ref "D5") (pin "2") (pinfunction "C2_2") (pintype "passive"))
      (node (ref "D6") (pin "2") (pinfunction "C2_2") (pintype "passive"))
      (node (ref "IC1") (pin "4") (pinfunction "V+_4") (pintype "power_in"))
      (node (ref "IC8") (pin "8") (pinfunction "V+_8") (pintype "power_in"))
      (node (ref "J1") (pin "2") (pinfunction "2_2") (pintype "passive"))
      (node (ref "J1") (pin "4") (pinfunction "4_4") (pintype "passive"))
      (node (ref "J2") (pin "7") (pinfunction "S_7") (pintype "passive"))
      (node (ref "J5") (pin "3") (pinfunction "3_3") (pintype "passive"))
      (node (ref "R10") (pin "2") (pinfunction "2_2") (pintype "passive"))
      (node (ref "R11") (pin "2") (pinfunction "2_2") (pintype "passive"))
      (node (ref "R12") (pin "2") (pinfunction "2_2") (pintype "passive"))
      (node (ref "R63") (pin "2") (pinfunction "2_2") (pintype "passive"))
      (node (ref "R67") (pin "2") (pinfunction "2_2") (pintype "passive"))
      (node (ref "R9") (pin "2") (pinfunction "2_2") (pintype "passive"))
    )
    (net (code "9") (name "12V") (class "Default")
      (node (ref "C12") (pin "1") (pinfunction "1_1") (pintype "passive"))
      (node (ref "C13") (pin "1") (pinfunction "1_1") (pintype "passive"))
      (node (ref "C24") (pin "1") (pinfunction "1_1") (pintype "passive"))
      (node (ref "D7") (pin "2") (pinfunction "C2_2") (pintype "passive"))
      (node (ref "D8") (pin "2") (pinfunction "C2_2") (pintype "passive"))
      (node (ref "IC11") (pin "3") (pinfunction "VIN_3") (pintype "bidirectional"))
      (node (ref "IC4") (pin "8") (pinfunction "V+_8") (pintype "power_in"))
      (node (ref "IC5") (pin "3") (pinfunction "C3_3") (pintype "passive"))
      (node (ref "IC7") (pin "3") (pinfunction "C3_3") (pintype "passive"))
      (node (ref "J11") (pin "+") (pinfunction "V+_+") (pintype "bidirectional"))
      (node (ref "J3") (pin "1") (pinfunction "S_1") (pintype "passive"))
      (node (ref "J3") (pin "2") (pinfunction "S_2") (pintype "passive"))
      (node (ref "R15") (pin "2") (pinfunction "2_2") (pintype "passive"))
      (node (ref "R17") (pin "2") (pinfunction "2_2") (pintype "passive"))
      (node (ref "R20") (pin "2") (pinfunction "2_2") (pintype "passive"))
      (node (ref "R23") (pin "2") (pinfunction "2_2") (pintype "passive"))
      (node (ref "R25") (pin "2") (pinfunction "2_2") (pintype "passive"))
      (node (ref "R29") (pin "2") (pinfunction "2_2") (pintype "passive"))
      (node (ref "R32") (pin "2") (pinfunction "2_2") (pintype "passive"))
      (node (ref "R35") (pin "2") (pinfunction "2_2") (pintype "passive"))
      (node (ref "R37") (pin "2") (pinfunction "2_2") (pintype "passive"))
      (node (ref "R41") (pin "2") (pinfunction "2_2") (pintype "passive"))
      (node (ref "R44") (pin "2") (pinfunction "2_2") (pintype "passive"))
      (node (ref "R47") (pin "2") (pinfunction "2_2") (pintype "passive"))
      (node (ref "R49") (pin "2") (pinfunction "2_2") (pintype "passive"))
      (node (ref "R82") (pin "2") (pinfunction "2_2") (pintype "passive"))
    )
    (net (code "10") (name "12V_FUSE_8") (class "Default")
      (node (ref "J22") (pin "1") (pinfunction "1_1") (pintype "passive"))
      (node (ref "J22") (pin "2") (pinfunction "2_2") (pintype "passive"))
      (node (ref "J6") (pin "9") (pinfunction "9_9") (pintype "bidirectional"))
      (node (ref "JP18") (pin "3") (pinfunction "3_3") (pintype "passive"))
    )
    (net (code "11") (name "12V_FUSE_16") (class "Default")
      (node (ref "J17") (pin "1") (pinfunction "1_1") (pintype "passive"))
      (node (ref "J17") (pin "2") (pinfunction "2_2") (pintype "passive"))
      (node (ref "J7") (pin "A") (pinfunction "A_A") (pintype "bidirectional"))
    )
    (net (code "12") (name "AC_RELAY{slash}VSS_TO_ECU") (class "Default")
      (node (ref "IC10") (pin "7") (pinfunction "COUT_7") (pintype "bidirectional"))
      (node (ref "J6") (pin "6") (pinfunction "6_6") (pintype "bidirectional"))
      (node (ref "Q1") (pin "1") (pinfunction "G_1") (pintype "bidirectional"))
      (node (ref "R15") (pin "1") (pinfunction "1_1") (pintype "passive"))
    )
    (net (code "13") (name "ADC1_IN") (class "Default")
      (node (ref "C1") (pin "1") (pinfunction "1_1") (pintype "passive"))
      (node (ref "IC2") (pin "1") (pinfunction "CH0_1") (pintype "bidirectional"))
      (node (ref "R2") (pin "16") (pinfunction "2_16") (pintype "passive"))
      (node (ref "R3") (pin "16") (pinfunction "2_16") (pintype "passive"))
    )
    (net (code "14") (name "ADC2_IN") (class "Default")
      (node (ref "C2") (pin "1") (pinfunction "1_1") (pintype "passive"))
      (node (ref "IC2") (pin "2") (pinfunction "CH1_2") (pintype "bidirectional"))
      (node (ref "R2") (pin "15") (pinfunction "2_15") (pintype "passive"))
      (node (ref "R3") (pin "15") (pinfunction "2_15") (pintype "passive"))
    )
    (net (code "15") (name "ADC3_IN") (class "Default")
      (node (ref "C3") (pin "1") (pinfunction "1_1") (pintype "passive"))
      (node (ref "IC2") (pin "3") (pinfunction "CH2_3") (pintype "bidirectional"))
      (node (ref "R2") (pin "14") (pinfunction "2_14") (pintype "passive"))
      (node (ref "R3") (pin "14") (pinfunction "2_14") (pintype "passive"))
    )
    (net (code "16") (name "ADC4_IN") (class "Default")
      (node (ref "C4") (pin "1") (pinfunction "1_1") (pintype "passive"))
      (node (ref "IC2") (pin "4") (pinfunction "CH3_4") (pintype "bidirectional"))
      (node (ref "R2") (pin "13") (pinfunction "2_13") (pintype "passive"))
      (node (ref "R3") (pin "13") (pinfunction "2_13") (pintype "passive"))
    )
    (net (code "17") (name "ADC5_IN") (class "Default")
      (node (ref "C17") (pin "1") (pinfunction "1_1") (pintype "passive"))
      (node (ref "IC2") (pin "5") (pinfunction "CH4_5") (pintype "bidirectional"))
      (node (ref "R2") (pin "12") (pinfunction "2_12") (pintype "passive"))
      (node (ref "R3") (pin "12") (pinfunction "2_12") (pintype "passive"))
    )
    (net (code "18") (name "ADC6_IN") (class "Default")
      (node (ref "C18") (pin "1") (pinfunction "1_1") (pintype "passive"))
      (node (ref "IC2") (pin "6") (pinfunction "CH5_6") (pintype "bidirectional"))
      (node (ref "R2") (pin "11") (pinfunction "2_11") (pintype "passive"))
      (node (ref "R3") (pin "11") (pinfunction "2_11") (pintype "passive"))
    )
    (net (code "19") (name "BLINKER_LEFT_P") (class "Default")
      (node (ref "J6") (pin "8") (pinfunction "8_8") (pintype "bidirectional"))
      (node (ref "JP7") (pin "2") (pinfunction "2_2") (pintype "passive"))
    )
    (net (code "20") (name "BLINKER_RIGHT_P") (class "Default")
      (node (ref "J6") (pin "7") (pinfunction "7_7") (pintype "bidirectional"))
      (node (ref "JP8") (pin "2") (pinfunction "2_2") (pintype "passive"))
    )
    (net (code "21") (name "BRAKE_FAILURE_N") (class "Default")
      (node (ref "J6") (pin "1") (pinfunction "1_1") (pintype "bidirectional"))
      (node (ref "JP4") (pin "2") (pinfunction "2_2") (pintype "passive"))
    )
    (net (code "22") (name "BULB_FAILURE_N") (class "Default")
      (node (ref "J6") (pin "12") (pinfunction "12_12") (pintype "bidirectional"))
      (node (ref "JP5") (pin "2") (pinfunction "2_2") (pintype "passive"))
    )
    (net (code "23") (name "CANH") (class "Default")
      (node (ref "D9") (pin "1") (pinfunction "1_1") (pintype "passive"))
      (node (ref "IC12") (pin "7") (pinfunction "CANH_7") (pintype "bidirectional"))
      (node (ref "J8") (pin "1") (pinfunction "1_1") (pintype "passive"))
      (node (ref "R77") (pin "2") (pinfunction "2_2") (pintype "passive"))
    )
    (net (code "24") (name "CANL") (class "Default")
      (node (ref "D9") (pin "2") (pinfunction "2_2") (pintype "passive"))
      (node (ref "IC12") (pin "6") (pinfunction "CANL_6") (pintype "bidirectional"))
      (node (ref "J8") (pin "2") (pinfunction "2_2") (pintype "passive"))
      (node (ref "R77") (pin "1") (pinfunction "1_1") (pintype "passive"))
    )
    (net (code "25") (name "CHARGING_N") (class "Default")
      (node (ref "J6") (pin "11") (pinfunction "11_11") (pintype "bidirectional"))
      (node (ref "JP6") (pin "2") (pinfunction "2_2") (pintype "passive"))
      (node (ref "R82") (pin "1") (pinfunction "1_1") (pintype "passive"))
    )
    (net (code "26") (name "CHECK_ENGINE_N") (class "Default")
      (node (ref "J14") (pin "1") (pinfunction "1_1") (pintype "passive"))
      (node (ref "JP10") (pin "2") (pinfunction "2_2") (pintype "passive"))
    )
    (net (code "27") (name "CONN_32_PIN3") (class "Default")
      (node (ref "J7") (pin "3") (pinfunction "3_3") (pintype "bidirectional"))
      (node (ref "JP12") (pin "2") (pinfunction "2_2") (pintype "passive"))
    )
    (net (code "28") (name "COOLANT_TEMP_SENSOR") (class "Default")
      (node (ref "J6") (pin "2") (pinfunction "2_2") (pintype "bidirectional"))
      (node (ref "JP13") (pin "3") (pinfunction "3_3") (pintype "passive"))
    )
    (net (code "29") (name "DIMMER_VOUT") (class "Default")
      (node (ref "J6") (pin "10") (pinfunction "10_10") (pintype "bidirectional"))
      (node (ref "JP17") (pin "3") (pinfunction "3_3") (pintype "passive"))
    )
    (net (code "30") (name "FUEL_LVL_SENDER") (class "Default")
      (node (ref "J7") (pin "1") (pinfunction "1_1") (pintype "bidirectional"))
      (node (ref "JP14") (pin "3") (pinfunction "3_3") (pintype "passive"))
    )
    (net (code "31") (name "GND") (class "Default")
      (node (ref "BT1") (pin "GND") (pinfunction "-_GND") (pintype "power_in"))
      (node (ref "C1") (pin "2") (pinfunction "2_2") (pintype "passive"))
      (node (ref "C10") (pin "2") (pinfunction "2_2") (pintype "passive"))
      (node (ref "C11") (pin "2") (pinfunction "2_2") (pintype "passive"))
      (node (ref "C14") (pin "2") (pinfunction "2_2") (pintype "passive"))
      (node (ref "C15") (pin "2") (pinfunction "2_2") (pintype "passive"))
      (node (ref "C16") (pin "2") (pinfunction "2_2") (pintype "passive"))
      (node (ref "C17") (pin "2") (pinfunction "2_2") (pintype "passive"))
      (node (ref "C18") (pin "2") (pinfunction "2_2") (pintype "passive"))
      (node (ref "C19") (pin "2") (pinfunction "2_2") (pintype "passive"))
      (node (ref "C2") (pin "2") (pinfunction "2_2") (pintype "passive"))
      (node (ref "C20") (pin "2") (pinfunction "2_2") (pintype "passive"))
      (node (ref "C3") (pin "2") (pinfunction "2_2") (pintype "passive"))
      (node (ref "C30") (pin "2") (pinfunction "2_2") (pintype "passive"))
      (node (ref "C31") (pin "2") (pinfunction "2_2") (pintype "passive"))
      (node (ref "C32") (pin "1") (pinfunction "1_1") (pintype "passive"))
      (node (ref "C33") (pin "2") (pinfunction "2_2") (pintype "passive"))
      (node (ref "C4") (pin "2") (pinfunction "2_2") (pintype "passive"))
      (node (ref "C5") (pin "2") (pinfunction "2_2") (pintype "passive"))
      (node (ref "C6") (pin "2") (pinfunction "2_2") (pintype "passive"))
      (node (ref "C7") (pin "2") (pinfunction "2_2") (pintype "passive"))
      (node (ref "C8") (pin "2") (pinfunction "2_2") (pintype "passive"))
      (node (ref "C9") (pin "2") (pinfunction "2_2") (pintype "passive"))
      (node (ref "D1") (pin "1") (pinfunction "A1_1") (pintype "passive"))
      (node (ref "D2") (pin "1") (pinfunction "A1_1") (pintype "passive"))
      (node (ref "D3") (pin "1") (pinfunction "A1_1") (pintype "passive"))
      (node (ref "D4") (pin "1") (pinfunction "A1_1") (pintype "passive"))
      (node (ref "D5") (pin "1") (pinfunction "A1_1") (pintype "passive"))
      (node (ref "D6") (pin "1") (pinfunction "A1_1") (pintype "passive"))
      (node (ref "D9") (pin "3") (pinfunction "3_3") (pintype "passive"))
      (node (ref "IC1") (pin "11") (pinfunction "V-_11") (pintype "power_in"))
      (node (ref "IC12") (pin "2") (pinfunction "GND_2") (pintype "bidirectional"))
      (node (ref "IC13") (pin "9") (pinfunction "VSS_9") (pintype "power_in"))
      (node (ref "IC2") (pin "14") (pinfunction "AGND_14") (pintype "bidirectional"))
      (node (ref "IC2") (pin "9") (pinfunction "DGND_9") (pintype "bidirectional"))
      (node (ref "IC3") (pin "10") (pinfunction "VSS_10") (pintype "power_in"))
      (node (ref "IC3") (pin "15") (pinfunction "A0_15") (pintype "input"))
      (node (ref "IC3") (pin "16") (pinfunction "A1_16") (pintype "input"))
      (node (ref "IC3") (pin "17") (pinfunction "A2_17") (pintype "input"))
      (node (ref "IC5") (pin "5") (pinfunction "A5_5") (pintype "passive"))
      (node (ref "IC6") (pin "3") (pinfunction "+IN_3") (pintype "input"))
      (node (ref "IC6") (pin "4") (pinfunction "V-_4") (pintype "power_in"))
      (node (ref "IC6") (pin "5") (pinfunction "+IN_5") (pintype "input"))
      (node (ref "IC7") (pin "5") (pinfunction "A5_5") (pintype "passive"))
      (node (ref "IC8") (pin "4") (pinfunction "V-_4") (pintype "power_in"))
      (node (ref "IC9") (pin "5") (pinfunction "GND_5") (pintype "power_in"))
      (node (ref "J1") (pin "14") (pinfunction "14_14") (pintype "passive"))
      (node (ref "J1") (pin "20") (pinfunction "20_20") (pintype "passive"))
      (node (ref "J1") (pin "25") (pinfunction "25_25") (pintype "passive"))
      (node (ref "J1") (pin "30") (pinfunction "30_30") (pintype "passive"))
      (node (ref "J1") (pin "39") (pinfunction "39_39") (pintype "passive"))
      (node (ref "J1") (pin "6") (pinfunction "6_6") (pintype "passive"))
      (node (ref "J1") (pin "9") (pinfunction "9_9") (pintype "passive"))
      (node (ref "J16") (pin "3") (pinfunction "3_3") (pintype "passive"))
      (node (ref "J2") (pin "8") (pinfunction "S_8") (pintype "passive"))
      (node (ref "J5") (pin "1") (pinfunction "1_1") (pintype "passive"))
      (node (ref "J9") (pin "6") (pinfunction "S_6") (pintype "passive"))
      (node (ref "OK1") (pin "12") (pinfunction "EMIT_12") (pintype "passive"))
      (node (ref "OK1") (pin "13") (pinfunction "EMIT_13") (pintype "passive"))
      (node (ref "OK1") (pin "16") (pinfunction "EMIT_16") (pintype "passive"))
      (node (ref "OK1") (pin "9") (pinfunction "EMIT_9") (pintype "passive"))
      (node (ref "OK2") (pin "12") (pinfunction "EMIT_12") (pintype "passive"))
      (node (ref "OK2") (pin "13") (pinfunction "EMIT_13") (pintype "passive"))
      (node (ref "OK2") (pin "16") (pinfunction "EMIT_16") (pintype "passive"))
      (node (ref "OK2") (pin "9") (pinfunction "EMIT_9") (pintype "passive"))
      (node (ref "OK3") (pin "12") (pinfunction "EMIT_12") (pintype "passive"))
      (node (ref "OK3") (pin "13") (pinfunction "EMIT_13") (pintype "passive"))
      (node (ref "OK3") (pin "16") (pinfunction "EMIT_16") (pintype "passive"))
      (node (ref "OK3") (pin "9") (pinfunction "EMIT_9") (pintype "passive"))
      (node (ref "Q1") (pin "2") (pinfunction "S_2") (pintype "bidirectional"))
      (node (ref "Q2") (pin "2") (pinfunction "S_2") (pintype "bidirectional"))
      (node (ref "R3") (pin "1") (pinfunction "1_1") (pintype "passive"))
      (node (ref "R3") (pin "2") (pinfunction "1_2") (pintype "passive"))
      (node (ref "R3") (pin "3") (pinfunction "1_3") (pintype "passive"))
      (node (ref "R3") (pin "4") (pinfunction "1_4") (pintype "passive"))
      (node (ref "R3") (pin "5") (pinfunction "1_5") (pintype "passive"))
      (node (ref "R3") (pin "6") (pinfunction "1_6") (pintype "passive"))
      (node (ref "R80") (pin "2") (pinfunction "2_2") (pintype "passive"))
      (node (ref "S1") (pin "1") (pinfunction "1_1") (pintype "passive"))
    )
    (net (code "32") (name "GND-ISO") (class "Default")
      (node (ref "C12") (pin "2") (pinfunction "2_2") (pintype "passive"))
      (node (ref "C13") (pin "2") (pinfunction "2_2") (pintype "passive"))
      (node (ref "C23") (pin "2") (pinfunction "2_2") (pintype "passive"))
      (node (ref "C24") (pin "2") (pinfunction "2_2") (pintype "passive"))
      (node (ref "C25") (pin "2") (pinfunction "2_2") (pintype "passive"))
      (node (ref "C27") (pin "2") (pinfunction "2_2") (pintype "passive"))
      (node (ref "C28") (pin "1") (pinfunction "1_1") (pintype "passive"))
      (node (ref "D7") (pin "1") (pinfunction "A1_1") (pintype "passive"))
      (node (ref "D8") (pin "1") (pinfunction "A1_1") (pintype "passive"))
      (node (ref "IC10") (pin "5") (pinfunction "GND_5") (pintype "bidirectional"))
      (node (ref "IC11") (pin "1") (pinfunction "GND_1") (pintype "bidirectional"))
      (node (ref "IC4") (pin "4") (pinfunction "V-_4") (pintype "power_in"))
      (node (ref "IC5") (pin "1") (pinfunction "C1_1") (pintype "passive"))
      (node (ref "IC7") (pin "1") (pinfunction "C1_1") (pintype "passive"))
      (node (ref "J20") (pin "1") (pinfunction "1_1") (pintype "passive"))
      (node (ref "J20") (pin "2") (pinfunction "2_2") (pintype "passive"))
      (node (ref "J21") (pin "1") (pinfunction "1_1") (pintype "passive"))
      (node (ref "J21") (pin "2") (pinfunction "2_2") (pintype "passive"))
      (node (ref "J3") (pin "3") (pinfunction "S_3") (pintype "passive"))
      (node (ref "J3") (pin "4") (pinfunction "S_4") (pintype "passive"))
      (node (ref "J7") (pin "4") (pinfunction "4_4") (pintype "bidirectional"))
      (node (ref "JP15") (pin "2") (pinfunction "2_2") (pintype "passive"))
      (node (ref "JP21") (pin "1") (pinfunction "1_1") (pintype "passive"))
      (node (ref "R14") (pin "2") (pinfunction "2_2") (pintype "passive"))
      (node (ref "R18") (pin "1") (pinfunction "1_1") (pintype "passive"))
      (node (ref "R21") (pin "1") (pinfunction "1_1") (pintype "passive"))
      (node (ref "R24") (pin "1") (pinfunction "1_1") (pintype "passive"))
      (node (ref "R26") (pin "1") (pinfunction "1_1") (pintype "passive"))
      (node (ref "R30") (pin "1") (pinfunction "1_1") (pintype "passive"))
      (node (ref "R33") (pin "1") (pinfunction "1_1") (pintype "passive"))
      (node (ref "R36") (pin "1") (pinfunction "1_1") (pintype "passive"))
      (node (ref "R38") (pin "1") (pinfunction "1_1") (pintype "passive"))
      (node (ref "R42") (pin "1") (pinfunction "1_1") (pintype "passive"))
      (node (ref "R45") (pin "1") (pinfunction "1_1") (pintype "passive"))
      (node (ref "R48") (pin "1") (pinfunction "1_1") (pintype "passive"))
      (node (ref "R50") (pin "1") (pinfunction "1_1") (pintype "passive"))
      (node (ref "R53") (pin "1") (pinfunction "1_1") (pintype "passive"))
      (node (ref "R59") (pin "1") (pinfunction "1_1") (pintype "passive"))
      (node (ref "R72") (pin "1") (pinfunction "1_1") (pintype "passive"))
      (node (ref "R74") (pin "1") (pinfunction "1_1") (pintype "passive"))
    )
    (net (code "33") (name "GPIO6") (class "Default")
      (node (ref "J1") (pin "31") (pinfunction "31_31") (pintype "passive"))
      (node (ref "J16") (pin "2") (pinfunction "2_2") (pintype "passive"))
      (node (ref "R76") (pin "1") (pinfunction "1_1") (pintype "passive"))
    )
    (net (code "34") (name "GPIO13") (class "Default")
      (node (ref "J1") (pin "33") (pinfunction "33_33") (pintype "passive"))
    )
    (net (code "35") (name "GPIO17") (class "Default")
      (node (ref "J1") (pin "11") (pinfunction "11_11") (pintype "passive"))
    )
    (net (code "36") (name "GPIO18") (class "Default")
      (node (ref "J1") (pin "12") (pinfunction "12_12") (pintype "passive"))
      (node (ref "J5") (pin "2") (pinfunction "2_2") (pintype "passive"))
      (node (ref "R60") (pin "1") (pinfunction "1_1") (pintype "passive"))
    )
    (net (code "37") (name "GPIO19") (class "Default")
      (node (ref "J1") (pin "35") (pinfunction "35_35") (pintype "passive"))
      (node (ref "Q2") (pin "3") (pinfunction "D_3") (pintype "bidirectional"))
      (node (ref "R54") (pin "1") (pinfunction "1_1") (pintype "passive"))
    )
    (net (code "38") (name "GPIO22") (class "Default")
      (node (ref "J1") (pin "15") (pinfunction "15_15") (pintype "passive"))
    )
    (net (code "39") (name "GPIO25") (class "Default")
      (node (ref "IC13") (pin "12") (pinfunction "INT_12") (pintype "output"))
      (node (ref "J1") (pin "22") (pinfunction "22_22") (pintype "passive"))
    )
    (net (code "40") (name "GPIO26") (class "Default")
      (node (ref "J1") (pin "37") (pinfunction "37_37") (pintype "passive"))
    )
    (net (code "41") (name "GPIO27") (class "Default")
      (node (ref "J1") (pin "13") (pinfunction "13_13") (pintype "passive"))
    )
    (net (code "42") (name "HIGH_BEAM_P") (class "Default")
      (node (ref "J6") (pin "3") (pinfunction "3_3") (pintype "bidirectional"))
      (node (ref "JP3") (pin "2") (pinfunction "2_2") (pintype "passive"))
    )
    (net (code "43") (name "IN1N") (class "Default")
      (node (ref "JP1") (pin "3") (pinfunction "3_3") (pintype "passive"))
      (node (ref "OK1") (pin "2") (pinfunction "C_2") (pintype "passive"))
      (node (ref "R18") (pin "2") (pinfunction "2_2") (pintype "passive"))
    )
    (net (code "44") (name "IN1P") (class "Default")
      (node (ref "JP1") (pin "1") (pinfunction "1_1") (pintype "passive"))
      (node (ref "OK1") (pin "1") (pinfunction "A_1") (pintype "passive"))
      (node (ref "R17") (pin "1") (pinfunction "1_1") (pintype "passive"))
    )
    (net (code "45") (name "IN2N") (class "Default")
      (node (ref "JP2") (pin "3") (pinfunction "3_3") (pintype "passive"))
      (node (ref "OK1") (pin "3") (pinfunction "C_3") (pintype "passive"))
      (node (ref "R21") (pin "2") (pinfunction "2_2") (pintype "passive"))
    )
    (net (code "46") (name "IN2P") (class "Default")
      (node (ref "JP2") (pin "1") (pinfunction "1_1") (pintype "passive"))
      (node (ref "OK1") (pin "4") (pinfunction "A_4") (pintype "passive"))
      (node (ref "R20") (pin "1") (pinfunction "1_1") (pintype "passive"))
    )
    (net (code "47") (name "IN3N") (class "Default")
      (node (ref "JP3") (pin "3") (pinfunction "3_3") (pintype "passive"))
      (node (ref "OK1") (pin "6") (pinfunction "C_6") (pintype "passive"))
      (node (ref "R24") (pin "2") (pinfunction "2_2") (pintype "passive"))
    )
    (net (code "48") (name "IN3P") (class "Default")
      (node (ref "JP3") (pin "1") (pinfunction "1_1") (pintype "passive"))
      (node (ref "OK1") (pin "5") (pinfunction "A_5") (pintype "passive"))
      (node (ref "R23") (pin "1") (pinfunction "1_1") (pintype "passive"))
    )
    (net (code "49") (name "IN4N") (class "Default")
      (node (ref "JP4") (pin "3") (pinfunction "3_3") (pintype "passive"))
      (node (ref "OK1") (pin "7") (pinfunction "C_7") (pintype "passive"))
      (node (ref "R26") (pin "2") (pinfunction "2_2") (pintype "passive"))
    )
    (net (code "50") (name "IN4P") (class "Default")
      (node (ref "JP4") (pin "1") (pinfunction "1_1") (pintype "passive"))
      (node (ref "OK1") (pin "8") (pinfunction "A_8") (pintype "passive"))
      (node (ref "R25") (pin "1") (pinfunction "1_1") (pintype "passive"))
    )
    (net (code "51") (name "IN5N") (class "Default")
      (node (ref "JP5") (pin "3") (pinfunction "3_3") (pintype "passive"))
      (node (ref "OK2") (pin "2") (pinfunction "C_2") (pintype "passive"))
      (node (ref "R30") (pin "2") (pinfunction "2_2") (pintype "passive"))
    )
    (net (code "52") (name "IN5P") (class "Default")
      (node (ref "JP5") (pin "1") (pinfunction "1_1") (pintype "passive"))
      (node (ref "OK2") (pin "1") (pinfunction "A_1") (pintype "passive"))
      (node (ref "R29") (pin "1") (pinfunction "1_1") (pintype "passive"))
    )
    (net (code "53") (name "IN6N") (class "Default")
      (node (ref "JP6") (pin "3") (pinfunction "3_3") (pintype "passive"))
      (node (ref "OK2") (pin "3") (pinfunction "C_3") (pintype "passive"))
      (node (ref "R33") (pin "2") (pinfunction "2_2") (pintype "passive"))
    )
    (net (code "54") (name "IN6P") (class "Default")
      (node (ref "JP6") (pin "1") (pinfunction "1_1") (pintype "passive"))
      (node (ref "OK2") (pin "4") (pinfunction "A_4") (pintype "passive"))
      (node (ref "R32") (pin "1") (pinfunction "1_1") (pintype "passive"))
    )
    (net (code "55") (name "IN7N") (class "Default")
      (node (ref "JP7") (pin "3") (pinfunction "3_3") (pintype "passive"))
      (node (ref "OK2") (pin "6") (pinfunction "C_6") (pintype "passive"))
      (node (ref "R36") (pin "2") (pinfunction "2_2") (pintype "passive"))
    )
    (net (code "56") (name "IN7P") (class "Default")
      (node (ref "JP7") (pin "1") (pinfunction "1_1") (pintype "passive"))
      (node (ref "OK2") (pin "5") (pinfunction "A_5") (pintype "passive"))
      (node (ref "R35") (pin "1") (pinfunction "1_1") (pintype "passive"))
    )
    (net (code "57") (name "IN8N") (class "Default")
      (node (ref "JP8") (pin "3") (pinfunction "3_3") (pintype "passive"))
      (node (ref "OK2") (pin "7") (pinfunction "C_7") (pintype "passive"))
      (node (ref "R38") (pin "2") (pinfunction "2_2") (pintype "passive"))
    )
    (net (code "58") (name "IN8P") (class "Default")
      (node (ref "JP8") (pin "1") (pinfunction "1_1") (pintype "passive"))
      (node (ref "OK2") (pin "8") (pinfunction "A_8") (pintype "passive"))
      (node (ref "R37") (pin "1") (pinfunction "1_1") (pintype "passive"))
    )
    (net (code "59") (name "IN9N") (class "Default")
      (node (ref "JP9") (pin "3") (pinfunction "3_3") (pintype "passive"))
      (node (ref "OK3") (pin "2") (pinfunction "C_2") (pintype "passive"))
      (node (ref "R42") (pin "2") (pinfunction "2_2") (pintype "passive"))
    )
    (net (code "60") (name "IN9P") (class "Default")
      (node (ref "JP9") (pin "1") (pinfunction "1_1") (pintype "passive"))
      (node (ref "OK3") (pin "1") (pinfunction "A_1") (pintype "passive"))
      (node (ref "R41") (pin "1") (pinfunction "1_1") (pintype "passive"))
    )
    (net (code "61") (name "IN10N") (class "Default")
      (node (ref "JP10") (pin "3") (pinfunction "3_3") (pintype "passive"))
      (node (ref "OK3") (pin "3") (pinfunction "C_3") (pintype "passive"))
      (node (ref "R45") (pin "2") (pinfunction "2_2") (pintype "passive"))
    )
    (net (code "62") (name "IN10P") (class "Default")
      (node (ref "JP10") (pin "1") (pinfunction "1_1") (pintype "passive"))
      (node (ref "OK3") (pin "4") (pinfunction "A_4") (pintype "passive"))
      (node (ref "R44") (pin "1") (pinfunction "1_1") (pintype "passive"))
    )
    (net (code "63") (name "IN11N") (class "Default")
      (node (ref "JP11") (pin "3") (pinfunction "3_3") (pintype "passive"))
      (node (ref "OK3") (pin "6") (pinfunction "C_6") (pintype "passive"))
      (node (ref "R48") (pin "2") (pinfunction "2_2") (pintype "passive"))
    )
    (net (code "64") (name "IN11P") (class "Default")
      (node (ref "JP11") (pin "1") (pinfunction "1_1") (pintype "passive"))
      (node (ref "OK3") (pin "5") (pinfunction "A_5") (pintype "passive"))
      (node (ref "R47") (pin "1") (pinfunction "1_1") (pintype "passive"))
    )
    (net (code "65") (name "IN12N") (class "Default")
      (node (ref "JP12") (pin "3") (pinfunction "3_3") (pintype "passive"))
      (node (ref "OK3") (pin "7") (pinfunction "C_7") (pintype "passive"))
      (node (ref "R50") (pin "2") (pinfunction "2_2") (pintype "passive"))
    )
    (net (code "66") (name "IN12P") (class "Default")
      (node (ref "JP12") (pin "1") (pinfunction "1_1") (pintype "passive"))
      (node (ref "OK3") (pin "8") (pinfunction "A_8") (pintype "passive"))
      (node (ref "R49") (pin "1") (pinfunction "1_1") (pintype "passive"))
    )
    (net (code "67") (name "Net-(BT1-+)") (class "Default")
      (node (ref "BT1") (pin "PWR@1") (pinfunction "+_PWR@1") (pintype "power_in"))
      (node (ref "IC9") (pin "3") (pinfunction "VBKP_3") (pintype "power_in"))
    )
    (net (code "68") (name "Net-(D1-C1A2)") (class "Default")
      (node (ref "D1") (pin "3") (pinfunction "C1A2_3") (pintype "passive"))
      (node (ref "IC1") (pin "3") (pinfunction "+IN_3") (pintype "input"))
      (node (ref "R1") (pin "2") (pinfunction "2_2") (pintype "passive"))
    )
    (net (code "69") (name "Net-(D2-C1A2)") (class "Default")
      (node (ref "D2") (pin "3") (pinfunction "C1A2_3") (pintype "passive"))
      (node (ref "IC1") (pin "5") (pinfunction "+IN_5") (pintype "input"))
      (node (ref "R4") (pin "2") (pinfunction "2_2") (pintype "passive"))
    )
    (net (code "70") (name "Net-(D3-C1A2)") (class "Default")
      (node (ref "D3") (pin "3") (pinfunction "C1A2_3") (pintype "passive"))
      (node (ref "IC1") (pin "10") (pinfunction "+IN_10") (pintype "input"))
      (node (ref "R6") (pin "2") (pinfunction "2_2") (pintype "passive"))
    )
    (net (code "71") (name "Net-(D4-C1A2)") (class "Default")
      (node (ref "D4") (pin "3") (pinfunction "C1A2_3") (pintype "passive"))
      (node (ref "IC1") (pin "12") (pinfunction "+IN_12") (pintype "input"))
      (node (ref "R8") (pin "2") (pinfunction "2_2") (pintype "passive"))
    )
    (net (code "72") (name "Net-(D5-C1A2)") (class "Default")
      (node (ref "D5") (pin "3") (pinfunction "C1A2_3") (pintype "passive"))
      (node (ref "IC8") (pin "3") (pinfunction "+IN_3") (pintype "input"))
      (node (ref "R65") (pin "2") (pinfunction "2_2") (pintype "passive"))
    )
    (net (code "73") (name "Net-(D6-C1A2)") (class "Default")
      (node (ref "D6") (pin "3") (pinfunction "C1A2_3") (pintype "passive"))
      (node (ref "IC8") (pin "5") (pinfunction "+IN_5") (pintype "input"))
      (node (ref "R69") (pin "2") (pinfunction "2_2") (pintype "passive"))
    )
    (net (code "74") (name "Net-(D7-C1A2)") (class "Default")
      (node (ref "D7") (pin "3") (pinfunction "C1A2_3") (pintype "passive"))
      (node (ref "IC4") (pin "3") (pinfunction "+IN_3") (pintype "input"))
      (node (ref "R57") (pin "2") (pinfunction "2_2") (pintype "passive"))
    )
    (net (code "75") (name "Net-(D8-C1A2)") (class "Default")
      (node (ref "D8") (pin "3") (pinfunction "C1A2_3") (pintype "passive"))
      (node (ref "IC4") (pin "5") (pinfunction "+IN_5") (pintype "input"))
      (node (ref "R58") (pin "2") (pinfunction "2_2") (pintype "passive"))
    )
    (net (code "76") (name "Net-(IC1A--IN)") (class "Default")
      (node (ref "IC1") (pin "1") (pinfunction "OUT_1") (pintype "output"))
      (node (ref "IC1") (pin "2") (pinfunction "-IN_2") (pintype "input"))
      (node (ref "R2") (pin "1") (pinfunction "1_1") (pintype "passive"))
    )
    (net (code "77") (name "Net-(IC1B--IN)") (class "Default")
      (node (ref "IC1") (pin "6") (pinfunction "-IN_6") (pintype "input"))
      (node (ref "IC1") (pin "7") (pinfunction "OUT_7") (pintype "output"))
      (node (ref "R2") (pin "2") (pinfunction "1_2") (pintype "passive"))
    )
    (net (code "78") (name "Net-(IC1C--IN)") (class "Default")
      (node (ref "IC1") (pin "8") (pinfunction "OUT_8") (pintype "output"))
      (node (ref "IC1") (pin "9") (pinfunction "-IN_9") (pintype "input"))
      (node (ref "R2") (pin "3") (pinfunction "1_3") (pintype "passive"))
    )
    (net (code "79") (name "Net-(IC1D--IN)") (class "Default")
      (node (ref "IC1") (pin "13") (pinfunction "-IN_13") (pintype "input"))
      (node (ref "IC1") (pin "14") (pinfunction "OUT_14") (pintype "output"))
      (node (ref "R2") (pin "4") (pinfunction "1_4") (pintype "passive"))
    )
    (net (code "80") (name "Net-(IC4A--IN)") (class "Default")
      (node (ref "IC4") (pin "2") (pinfunction "-IN_2") (pintype "input"))
      (node (ref "IC5") (pin "4") (pinfunction "A4_4") (pintype "passive"))
      (node (ref "R53") (pin "2") (pinfunction "2_2") (pintype "passive"))
    )
    (net (code "81") (name "Net-(IC4A-OUT)") (class "Default")
      (node (ref "IC4") (pin "1") (pinfunction "OUT_1") (pintype "output"))
      (node (ref "R55") (pin "1") (pinfunction "1_1") (pintype "passive"))
    )
    (net (code "82") (name "Net-(IC4B--IN)") (class "Default")
      (node (ref "IC4") (pin "6") (pinfunction "-IN_6") (pintype "input"))
      (node (ref "IC7") (pin "4") (pinfunction "A4_4") (pintype "passive"))
      (node (ref "R59") (pin "2") (pinfunction "2_2") (pintype "passive"))
    )
    (net (code "83") (name "Net-(IC4B-OUT)") (class "Default")
      (node (ref "IC4") (pin "7") (pinfunction "OUT_7") (pintype "output"))
      (node (ref "R61") (pin "1") (pinfunction "1_1") (pintype "passive"))
    )
    (net (code "84") (name "Net-(IC5-A2)") (class "Default")
      (node (ref "IC5") (pin "2") (pinfunction "A2_2") (pintype "passive"))
      (node (ref "R55") (pin "2") (pinfunction "2_2") (pintype "passive"))
    )
    (net (code "85") (name "Net-(IC5-C6)") (class "Default")
      (node (ref "C21") (pin "2") (pinfunction "2_2") (pintype "passive"))
      (node (ref "IC5") (pin "6") (pinfunction "C6_6") (pintype "passive"))
      (node (ref "IC6") (pin "2") (pinfunction "-IN_2") (pintype "input"))
      (node (ref "R56") (pin "1") (pinfunction "1_1") (pintype "passive"))
    )
    (net (code "86") (name "Net-(IC6B--IN)") (class "Default")
      (node (ref "C22") (pin "1") (pinfunction "1_1") (pintype "passive"))
      (node (ref "IC6") (pin "6") (pinfunction "-IN_6") (pintype "input"))
      (node (ref "IC7") (pin "6") (pinfunction "C6_6") (pintype "passive"))
      (node (ref "R62") (pin "1") (pinfunction "1_1") (pintype "passive"))
    )
    (net (code "87") (name "Net-(IC7-A2)") (class "Default")
      (node (ref "IC7") (pin "2") (pinfunction "A2_2") (pintype "passive"))
      (node (ref "R61") (pin "2") (pinfunction "2_2") (pintype "passive"))
    )
    (net (code "88") (name "Net-(IC8A--IN)") (class "Default")
      (node (ref "IC8") (pin "1") (pinfunction "OUT_1") (pintype "output"))
      (node (ref "IC8") (pin "2") (pinfunction "-IN_2") (pintype "input"))
      (node (ref "R2") (pin "5") (pinfunction "1_5") (pintype "passive"))
    )
    (net (code "89") (name "Net-(IC8B--IN)") (class "Default")
      (node (ref "IC8") (pin "6") (pinfunction "-IN_6") (pintype "input"))
      (node (ref "IC8") (pin "7") (pinfunction "OUT_7") (pintype "output"))
      (node (ref "R2") (pin "6") (pinfunction "1_6") (pintype "passive"))
    )
    (net (code "90") (name "Net-(IC9-SQW)") (class "Default")
      (node (ref "IC9") (pin "9") (pinfunction "SQW_9") (pintype "output"))
      (node (ref "R75") (pin "1") (pinfunction "1_1") (pintype "passive"))
    )
    (net (code "91") (name "Net-(IC9-X1)") (class "Default")
      (node (ref "IC9") (pin "1") (pinfunction "X1_1") (pintype "bidirectional"))
      (node (ref "Y1") (pin "2") (pinfunction "2_2") (pintype "passive"))
    )
    (net (code "92") (name "Net-(IC9-X2)") (class "Default")
      (node (ref "IC9") (pin "2") (pinfunction "X2_2") (pintype "bidirectional"))
      (node (ref "Y1") (pin "1") (pinfunction "1_1") (pintype "passive"))
    )
    (net (code "93") (name "Net-(IC9-~{RST})") (class "Default")
      (node (ref "IC9") (pin "4") (pinfunction "~{RST}_4") (pintype "input"))
      (node (ref "S1") (pin "2") (pinfunction "2_2") (pintype "passive"))
    )
    (net (code "94") (name "Net-(IC10-BIAS)") (class "Default")
      (node (ref "C27") (pin "1") (pinfunction "1_1") (pintype "passive"))
      (node (ref "C28") (pin "2") (pinfunction "2_2") (pintype "passive"))
      (node (ref "IC10") (pin "4") (pinfunction "BIAS_4") (pintype "bidirectional"))
      (node (ref "R13") (pin "1") (pinfunction "1_1") (pintype "passive"))
      (node (ref "R14") (pin "1") (pinfunction "1_1") (pintype "passive"))
    )
    (net (code "95") (name "Net-(IC10-IN+)") (class "Default")
      (node (ref "C26") (pin "1") (pinfunction "1_1") (pintype "passive"))
      (node (ref "IC10") (pin "1") (pinfunction "IN+_1") (pintype "bidirectional"))
      (node (ref "R5") (pin "2") (pinfunction "2_2") (pintype "passive"))
    )
    (net (code "96") (name "Net-(IC10-IN-)") (class "Default")
      (node (ref "C26") (pin "2") (pinfunction "2_2") (pintype "passive"))
      (node (ref "IC10") (pin "2") (pinfunction "IN-_2") (pintype "bidirectional"))
      (node (ref "R7") (pin "2") (pinfunction "2_2") (pintype "passive"))
    )
    (net (code "97") (name "Net-(IC10-INT_THRS)") (class "Default")
      (node (ref "IC10") (pin "6") (pinfunction "ZERO_EN_6") (pintype "bidirectional"))
      (node (ref "IC10") (pin "9") (pinfunction "INT_THRS_9") (pintype "bidirectional"))
      (node (ref "JP21") (pin "2") (pinfunction "2_2") (pintype "passive"))
    )
    (net (code "98") (name "Net-(IC12-RXD)") (class "Default")
      (node (ref "IC12") (pin "4") (pinfunction "RXD_4") (pintype "bidirectional"))
      (node (ref "IC13") (pin "2") (pinfunction "RXCAN_2") (pintype "input"))
    )
    (net (code "99") (name "Net-(IC12-S)") (class "Default")
      (node (ref "IC12") (pin "8") (pinfunction "S_8") (pintype "bidirectional"))
      (node (ref "R80") (pin "1") (pinfunction "1_1") (pintype "passive"))
    )
    (net (code "100") (name "Net-(IC12-TXD)") (class "Default")
      (node (ref "IC12") (pin "1") (pinfunction "TXD_1") (pintype "bidirectional"))
      (node (ref "IC13") (pin "1") (pinfunction "TXCAN_1") (pintype "output"))
    )
    (net (code "101") (name "Net-(IC13A-OSC1)") (class "Default")
      (node (ref "C32") (pin "2") (pinfunction "2_2") (pintype "passive"))
      (node (ref "IC13") (pin "8") (pinfunction "OSC1_8") (pintype "input"))
      (node (ref "X1") (pin "1") (pinfunction "1_1") (pintype "passive"))
    )
    (net (code "102") (name "Net-(IC13A-OSC2)") (class "Default")
      (node (ref "C33") (pin "1") (pinfunction "1_1") (pintype "passive"))
      (node (ref "IC13") (pin "7") (pinfunction "OSC2_7") (pintype "output"))
      (node (ref "X1") (pin "2") (pinfunction "2_2") (pintype "passive"))
    )
    (net (code "103") (name "Net-(IC13A-RESET)") (class "Default")
      (node (ref "IC13") (pin "17") (pinfunction "RESET_17") (pintype "input"))
      (node (ref "R81") (pin "1") (pinfunction "1_1") (pintype "passive"))
    )
    (net (code "104") (name "Net-(JP13-Pad2)") (class "Default")
      (node (ref "JP13") (pin "2") (pinfunction "2_2") (pintype "passive"))
      (node (ref "R1") (pin "1") (pinfunction "1_1") (pintype "passive"))
      (node (ref "R9") (pin "1") (pinfunction "1_1") (pintype "passive"))
    )
    (net (code "105") (name "Net-(JP14-Pad2)") (class "Default")
      (node (ref "JP14") (pin "2") (pinfunction "2_2") (pintype "passive"))
      (node (ref "R10") (pin "1") (pinfunction "1_1") (pintype "passive"))
      (node (ref "R4") (pin "1") (pinfunction "1_1") (pintype "passive"))
    )
    (net (code "106") (name "Net-(JP17-Pad2)") (class "Default")
      (node (ref "JP17") (pin "2") (pinfunction "2_2") (pintype "passive"))
      (node (ref "R73") (pin "1") (pinfunction "1_1") (pintype "passive"))
    )
    (net (code "107") (name "Net-(JP18-Pad2)") (class "Default")
      (node (ref "JP18") (pin "2") (pinfunction "2_2") (pintype "passive"))
      (node (ref "R71") (pin "1") (pinfunction "1_1") (pintype "passive"))
    )
    (net (code "108") (name "Net-(Q1-D)") (class "Default")
      (node (ref "Q1") (pin "3") (pinfunction "D_3") (pintype "bidirectional"))
      (node (ref "Q2") (pin "1") (pinfunction "G_1") (pintype "bidirectional"))
      (node (ref "R16") (pin "1") (pinfunction "1_1") (pintype "passive"))
    )
    (net (code "109") (name "Net-(R57-Pad1)") (class "Default")
      (node (ref "R57") (pin "1") (pinfunction "1_1") (pintype "passive"))
      (node (ref "R73") (pin "2") (pinfunction "2_2") (pintype "passive"))
      (node (ref "R74") (pin "2") (pinfunction "2_2") (pintype "passive"))
    )
    (net (code "110") (name "Net-(R58-Pad1)") (class "Default")
      (node (ref "R58") (pin "1") (pinfunction "1_1") (pintype "passive"))
      (node (ref "R71") (pin "2") (pinfunction "2_2") (pintype "passive"))
      (node (ref "R72") (pin "2") (pinfunction "2_2") (pintype "passive"))
    )
    (net (code "111") (name "OD_LAMP_AUTO_P") (class "Default")
      (node (ref "J13") (pin "1") (pinfunction "1_1") (pintype "passive"))
      (node (ref "JP9") (pin "2") (pinfunction "2_2") (pintype "passive"))
    )
    (net (code "112") (name "OD_LAMP_P") (class "Default")
      (node (ref "J6") (pin "4") (pinfunction "4_4") (pintype "bidirectional"))
      (node (ref "JP2") (pin "2") (pinfunction "2_2") (pintype "passive"))
    )
    (net (code "113") (name "OIL_PRESS_SW_N") (class "Default")
      (node (ref "J6") (pin "5") (pinfunction "5_5") (pintype "bidirectional"))
      (node (ref "JP1") (pin "2") (pinfunction "2_2") (pintype "passive"))
    )
    (net (code "114") (name "OUT1") (class "Default")
      (node (ref "IC3") (pin "21") (pinfunction "GPA0_21") (pintype "bidirectional"))
      (node (ref "OK1") (pin "15") (pinfunction "COL_15") (pintype "passive"))
      (node (ref "R19") (pin "1") (pinfunction "1_1") (pintype "passive"))
    )
    (net (code "115") (name "OUT2") (class "Default")
      (node (ref "IC3") (pin "22") (pinfunction "GPA1_22") (pintype "bidirectional"))
      (node (ref "OK1") (pin "14") (pinfunction "COL_14") (pintype "passive"))
      (node (ref "R22") (pin "1") (pinfunction "1_1") (pintype "passive"))
    )
    (net (code "116") (name "OUT3") (class "Default")
      (node (ref "IC3") (pin "23") (pinfunction "GPA2_23") (pintype "bidirectional"))
      (node (ref "OK1") (pin "11") (pinfunction "COL_11") (pintype "passive"))
      (node (ref "R27") (pin "1") (pinfunction "1_1") (pintype "passive"))
    )
    (net (code "117") (name "OUT4") (class "Default")
      (node (ref "IC3") (pin "24") (pinfunction "GPA3_24") (pintype "bidirectional"))
      (node (ref "OK1") (pin "10") (pinfunction "COL_10") (pintype "passive"))
      (node (ref "R28") (pin "1") (pinfunction "1_1") (pintype "passive"))
    )
    (net (code "118") (name "OUT5") (class "Default")
      (node (ref "IC3") (pin "28") (pinfunction "GPA7_28") (pintype "bidirectional"))
      (node (ref "OK2") (pin "15") (pinfunction "COL_15") (pintype "passive"))
      (node (ref "R31") (pin "1") (pinfunction "1_1") (pintype "passive"))
    )
    (net (code "119") (name "OUT6") (class "Default")
      (node (ref "IC3") (pin "27") (pinfunction "GPA6_27") (pintype "bidirectional"))
      (node (ref "OK2") (pin "14") (pinfunction "COL_14") (pintype "passive"))
      (node (ref "R34") (pin "1") (pinfunction "1_1") (pintype "passive"))
    )
    (net (code "120") (name "OUT7") (class "Default")
      (node (ref "IC3") (pin "26") (pinfunction "GPA5_26") (pintype "bidirectional"))
      (node (ref "OK2") (pin "11") (pinfunction "COL_11") (pintype "passive"))
      (node (ref "R39") (pin "1") (pinfunction "1_1") (pintype "passive"))
    )
    (net (code "121") (name "OUT8") (class "Default")
      (node (ref "IC3") (pin "25") (pinfunction "GPA4_25") (pintype "bidirectional"))
      (node (ref "OK2") (pin "10") (pinfunction "COL_10") (pintype "passive"))
      (node (ref "R40") (pin "1") (pinfunction "1_1") (pintype "passive"))
    )
    (net (code "122") (name "OUT9") (class "Default")
      (node (ref "IC3") (pin "1") (pinfunction "GPB0_1") (pintype "bidirectional"))
      (node (ref "OK3") (pin "15") (pinfunction "COL_15") (pintype "passive"))
      (node (ref "R43") (pin "1") (pinfunction "1_1") (pintype "passive"))
    )
    (net (code "123") (name "OUT10") (class "Default")
      (node (ref "IC3") (pin "2") (pinfunction "GPB1_2") (pintype "bidirectional"))
      (node (ref "OK3") (pin "14") (pinfunction "COL_14") (pintype "passive"))
      (node (ref "R46") (pin "1") (pinfunction "1_1") (pintype "passive"))
    )
    (net (code "124") (name "OUT11") (class "Default")
      (node (ref "IC3") (pin "3") (pinfunction "GPB2_3") (pintype "bidirectional"))
      (node (ref "OK3") (pin "11") (pinfunction "COL_11") (pintype "passive"))
      (node (ref "R51") (pin "1") (pinfunction "1_1") (pintype "passive"))
    )
    (net (code "125") (name "OUT12") (class "Default")
      (node (ref "IC3") (pin "4") (pinfunction "GPB3_4") (pintype "bidirectional"))
      (node (ref "OK3") (pin "10") (pinfunction "COL_10") (pintype "passive"))
      (node (ref "R52") (pin "1") (pinfunction "1_1") (pintype "passive"))
    )
    (net (code "126") (name "PARKING_BRAKE_N") (class "Default")
      (node (ref "J7") (pin "2") (pinfunction "2_2") (pintype "bidirectional"))
      (node (ref "JP11") (pin "2") (pinfunction "2_2") (pintype "passive"))
    )
    (net (code "127") (name "SCL") (class "Default")
      (node (ref "IC3") (pin "12") (pinfunction "SCL_12") (pintype "input"))
      (node (ref "IC9") (pin "7") (pinfunction "SCL_7") (pintype "bidirectional"))
      (node (ref "J1") (pin "5") (pinfunction "5_5") (pintype "passive"))
    )
    (net (code "128") (name "SDA") (class "Default")
      (node (ref "IC3") (pin "13") (pinfunction "SDA_13") (pintype "bidirectional"))
      (node (ref "IC9") (pin "6") (pinfunction "SDA_6") (pintype "bidirectional"))
      (node (ref "J1") (pin "3") (pinfunction "3_3") (pintype "passive"))
    )
    (net (code "129") (name "SENSOR1_IN") (class "Default")
      (node (ref "J2") (pin "4") (pinfunction "S_4") (pintype "passive"))
      (node (ref "JP13") (pin "1") (pinfunction "1_1") (pintype "passive"))
    )
    (net (code "130") (name "SENSOR2_IN") (class "Default")
      (node (ref "J2") (pin "3") (pinfunction "S_3") (pintype "passive"))
      (node (ref "JP14") (pin "1") (pinfunction "1_1") (pintype "passive"))
    )
    (net (code "131") (name "SENSOR3_IN") (class "Default")
      (node (ref "J2") (pin "2") (pinfunction "S_2") (pintype "passive"))
      (node (ref "R11") (pin "1") (pinfunction "1_1") (pintype "passive"))
      (node (ref "R6") (pin "1") (pinfunction "1_1") (pintype "passive"))
    )
    (net (code "132") (name "SENSOR4_IN") (class "Default")
      (node (ref "J2") (pin "1") (pinfunction "S_1") (pintype "passive"))
      (node (ref "R12") (pin "1") (pinfunction "1_1") (pintype "passive"))
      (node (ref "R8") (pin "1") (pinfunction "1_1") (pintype "passive"))
    )
    (net (code "133") (name "SENSOR5_IN") (class "Default")
      (node (ref "J2") (pin "5") (pinfunction "S_5") (pintype "passive"))
      (node (ref "R63") (pin "1") (pinfunction "1_1") (pintype "passive"))
      (node (ref "R65") (pin "1") (pinfunction "1_1") (pintype "passive"))
    )
    (net (code "134") (name "SENSOR6_IN") (class "Default")
      (node (ref "J2") (pin "6") (pinfunction "S_6") (pintype "passive"))
      (node (ref "R67") (pin "1") (pinfunction "1_1") (pintype "passive"))
      (node (ref "R69") (pin "1") (pinfunction "1_1") (pintype "passive"))
    )
    (net (code "135") (name "SIG_3V3_IN1") (class "Default")
      (node (ref "C21") (pin "1") (pinfunction "1_1") (pintype "passive"))
      (node (ref "IC2") (pin "7") (pinfunction "CH6_7") (pintype "bidirectional"))
      (node (ref "IC6") (pin "1") (pinfunction "OUT_1") (pintype "output"))
      (node (ref "R56") (pin "2") (pinfunction "2_2") (pintype "passive"))
    )
    (net (code "136") (name "SIG_3V3_IN2") (class "Default")
      (node (ref "C22") (pin "2") (pinfunction "2_2") (pintype "passive"))
      (node (ref "IC2") (pin "8") (pinfunction "CH7_8") (pintype "bidirectional"))
      (node (ref "IC6") (pin "7") (pinfunction "OUT_7") (pintype "output"))
      (node (ref "R62") (pin "2") (pinfunction "2_2") (pintype "passive"))
    )
    (net (code "137") (name "SIG_12V_IN1") (class "Default")
      (node (ref "JP17") (pin "1") (pinfunction "1_1") (pintype "passive"))
    )
    (net (code "138") (name "SIG_12V_IN2") (class "Default")
      (node (ref "JP18") (pin "1") (pinfunction "1_1") (pintype "passive"))
    )
    (net (code "139") (name "SPI_CE0_N") (class "Default")
      (node (ref "J1") (pin "24") (pinfunction "24_24") (pintype "passive"))
      (node (ref "JP16") (pin "3") (pinfunction "3_3") (pintype "passive"))
      (node (ref "JP22") (pin "3") (pinfunction "3_3") (pintype "passive"))
    )
    (net (code "140") (name "SPI_CE1_N") (class "Default")
      (node (ref "J1") (pin "26") (pinfunction "26_26") (pintype "passive"))
      (node (ref "JP16") (pin "1") (pinfunction "1_1") (pintype "passive"))
      (node (ref "JP22") (pin "1") (pinfunction "1_1") (pintype "passive"))
    )
    (net (code "141") (name "SPI_CLK") (class "Default")
      (node (ref "IC13") (pin "13") (pinfunction "SCK_13") (pintype "input"))
      (node (ref "IC2") (pin "13") (pinfunction "CLK_13") (pintype "bidirectional"))
      (node (ref "J1") (pin "23") (pinfunction "23_23") (pintype "passive"))
    )
    (net (code "142") (name "SPI_MISO") (class "Default")
      (node (ref "IC13") (pin "15") (pinfunction "SO_15") (pintype "output"))
      (node (ref "IC2") (pin "12") (pinfunction "DOUT_12") (pintype "bidirectional"))
      (node (ref "J1") (pin "21") (pinfunction "21_21") (pintype "passive"))
    )
    (net (code "143") (name "SPI_MOSI") (class "Default")
      (node (ref "IC13") (pin "14") (pinfunction "SI_14") (pintype "input"))
      (node (ref "IC2") (pin "11") (pinfunction "DIN_11") (pintype "bidirectional"))
      (node (ref "J1") (pin "19") (pinfunction "19_19") (pintype "passive"))
    )
    (net (code "144") (name "VCCA") (class "Default")
      (node (ref "C23") (pin "1") (pinfunction "1_1") (pintype "passive"))
      (node (ref "C25") (pin "1") (pinfunction "1_1") (pintype "passive"))
      (node (ref "IC10") (pin "10") (pinfunction "VCC_10") (pintype "bidirectional"))
      (node (ref "IC11") (pin "2") (pinfunction "VOUT_2") (pintype "bidirectional"))
      (node (ref "JP21") (pin "3") (pinfunction "3_3") (pintype "passive"))
      (node (ref "R13") (pin "2") (pinfunction "2_2") (pintype "passive"))
    )
    (net (code "145") (name "VSS+") (class "Default")
      (node (ref "J11") (pin "G") (pinfunction "VSS+_G") (pintype "bidirectional"))
      (node (ref "R5") (pin "1") (pinfunction "1_1") (pintype "passive"))
    )
    (net (code "146") (name "VSS-") (class "Default")
      (node (ref "J11") (pin "1") (pinfunction "VSS-_1") (pintype "bidirectional"))
      (node (ref "JP15") (pin "1") (pinfunction "1_1") (pintype "passive"))
      (node (ref "R7") (pin "1") (pinfunction "1_1") (pintype "passive"))
    )
    (net (code "147") (name "unconnected-(IC3-INTA-Pad20)") (class "Default")
      (node (ref "IC3") (pin "20") (pinfunction "INTA_20") (pintype "output"))
    )
    (net (code "148") (name "unconnected-(IC3-INTB-Pad19)") (class "Default")
      (node (ref "IC3") (pin "19") (pinfunction "INTB_19") (pintype "output"))
    )
    (net (code "149") (name "unconnected-(IC9-~{INT}-Pad8)") (class "Default")
      (node (ref "IC9") (pin "8") (pinfunction "~{INT}_8") (pintype "output"))
    )
    (net (code "150") (name "unconnected-(IC10-EXT-Pad8)") (class "Default")
      (node (ref "IC10") (pin "8") (pinfunction "EXT_8") (pintype "bidirectional"))
    )
    (net (code "151") (name "unconnected-(IC12-VREF-Pad5)") (class "Default")
      (node (ref "IC12") (pin "5") (pinfunction "VREF_5") (pintype "bidirectional"))
    )
    (net (code "152") (name "unconnected-(IC13A-CLKOUT-Pad3)") (class "Default")
      (node (ref "IC13") (pin "3") (pinfunction "CLKOUT_3") (pintype "output"))
    )
    (net (code "153") (name "unconnected-(IC13A-RX0BF-Pad11)") (class "Default")
      (node (ref "IC13") (pin "11") (pinfunction "RX0BF_11") (pintype "output"))
    )
    (net (code "154") (name "unconnected-(IC13A-RX1BF-Pad10)") (class "Default")
      (node (ref "IC13") (pin "10") (pinfunction "RX1BF_10") (pintype "output"))
    )
    (net (code "155") (name "unconnected-(IC13A-TX0RTS-Pad4)") (class "Default")
      (node (ref "IC13") (pin "4") (pinfunction "TX0RTS_4") (pintype "input"))
    )
    (net (code "156") (name "unconnected-(IC13A-TX1RTS-Pad5)") (class "Default")
      (node (ref "IC13") (pin "5") (pinfunction "TX1RTS_5") (pintype "input"))
    )
    (net (code "157") (name "unconnected-(IC13A-TX2RTS-Pad6)") (class "Default")
      (node (ref "IC13") (pin "6") (pinfunction "TX2RTS_6") (pintype "input"))
    )
    (net (code "158") (name "unconnected-(J1-Pad7)") (class "Default")
      (node (ref "J1") (pin "7") (pinfunction "7_7") (pintype "passive"))
    )
    (net (code "159") (name "unconnected-(J1-Pad8)") (class "Default")
      (node (ref "J1") (pin "8") (pinfunction "8_8") (pintype "passive"))
    )
    (net (code "160") (name "unconnected-(J1-Pad10)") (class "Default")
      (node (ref "J1") (pin "10") (pinfunction "10_10") (pintype "passive"))
    )
    (net (code "161") (name "unconnected-(J1-Pad16)") (class "Default")
      (node (ref "J1") (pin "16") (pinfunction "16_16") (pintype "passive"))
    )
    (net (code "162") (name "unconnected-(J1-Pad18)") (class "Default")
      (node (ref "J1") (pin "18") (pinfunction "18_18") (pintype "passive"))
    )
    (net (code "163") (name "unconnected-(J1-Pad27)") (class "Default")
      (node (ref "J1") (pin "27") (pinfunction "27_27") (pintype "passive"))
    )
    (net (code "164") (name "unconnected-(J1-Pad28)") (class "Default")
      (node (ref "J1") (pin "28") (pinfunction "28_28") (pintype "passive"))
    )
    (net (code "165") (name "unconnected-(J1-Pad29)") (class "Default")
      (node (ref "J1") (pin "29") (pinfunction "29_29") (pintype "passive"))
    )
    (net (code "166") (name "unconnected-(J1-Pad32)") (class "Default")
      (node (ref "J1") (pin "32") (pinfunction "32_32") (pintype "passive"))
    )
    (net (code "167") (name "unconnected-(J1-Pad34)") (class "Default")
      (node (ref "J1") (pin "34") (pinfunction "34_34") (pintype "passive"))
    )
    (net (code "168") (name "unconnected-(J1-Pad36)") (class "Default")
      (node (ref "J1") (pin "36") (pinfunction "36_36") (pintype "passive"))
    )
    (net (code "169") (name "unconnected-(J1-Pad38)") (class "Default")
      (node (ref "J1") (pin "38") (pinfunction "38_38") (pintype "passive"))
    )
    (net (code "170") (name "unconnected-(J1-Pad40)") (class "Default")
      (node (ref "J1") (pin "40") (pinfunction "40_40") (pintype "passive"))
    )
  )
)
